# oresat0-backplane.net
KiCad netlist of a schematic drawn in EAGLE
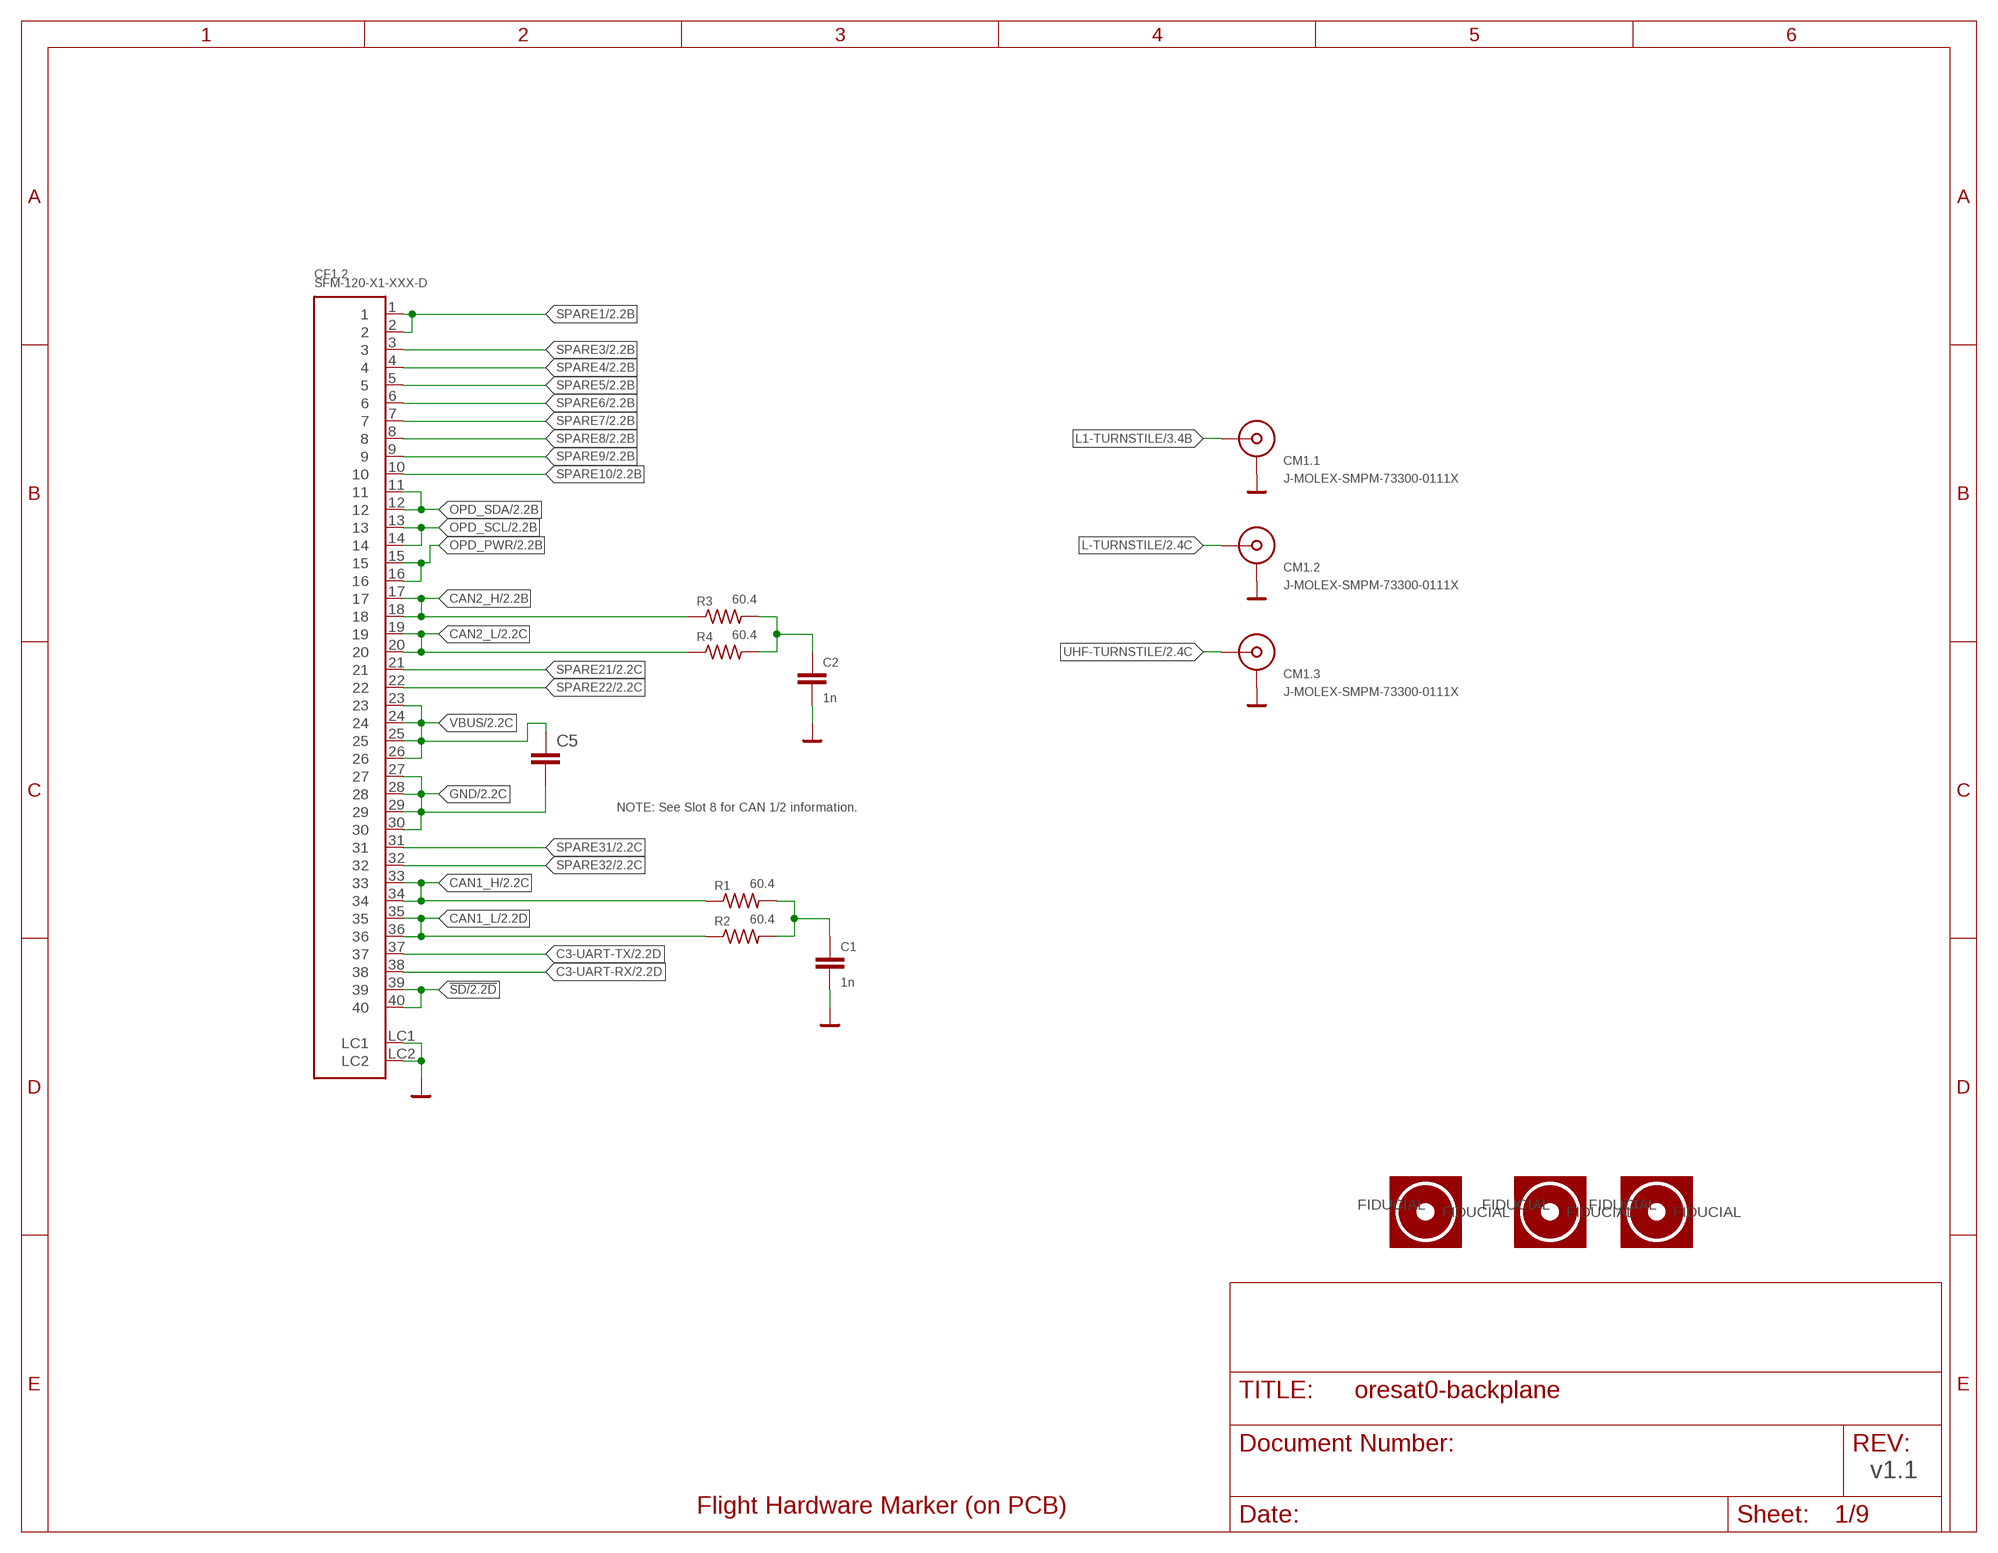
[diagram p0: schematic, sheet 1]
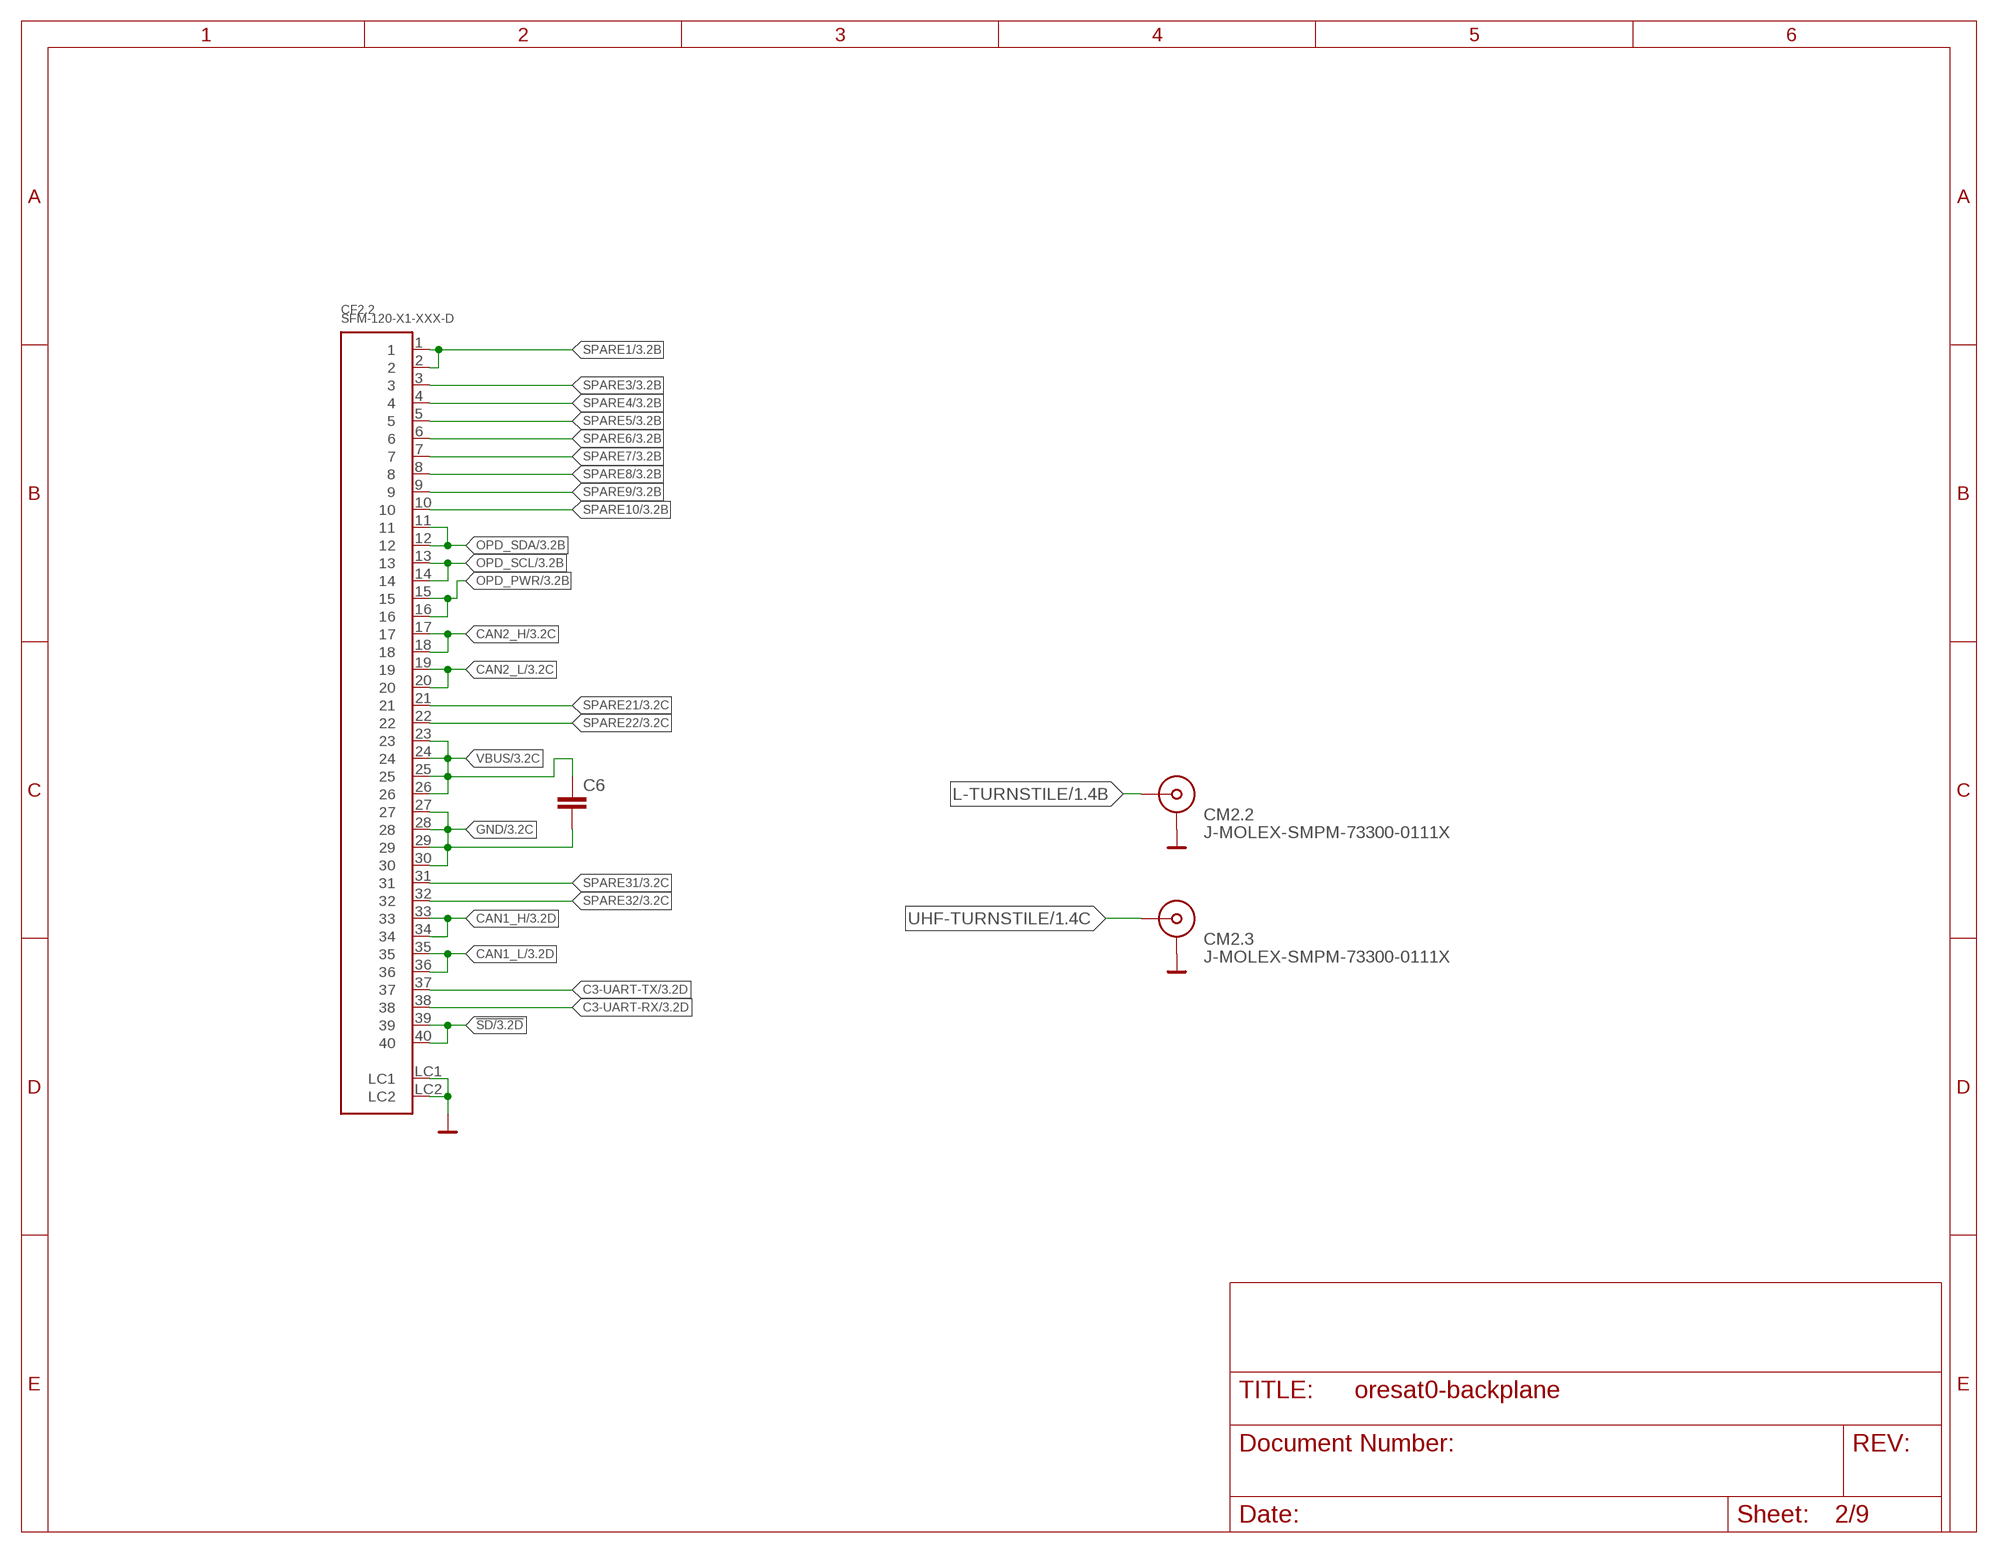
[diagram p1: schematic, sheet 2]
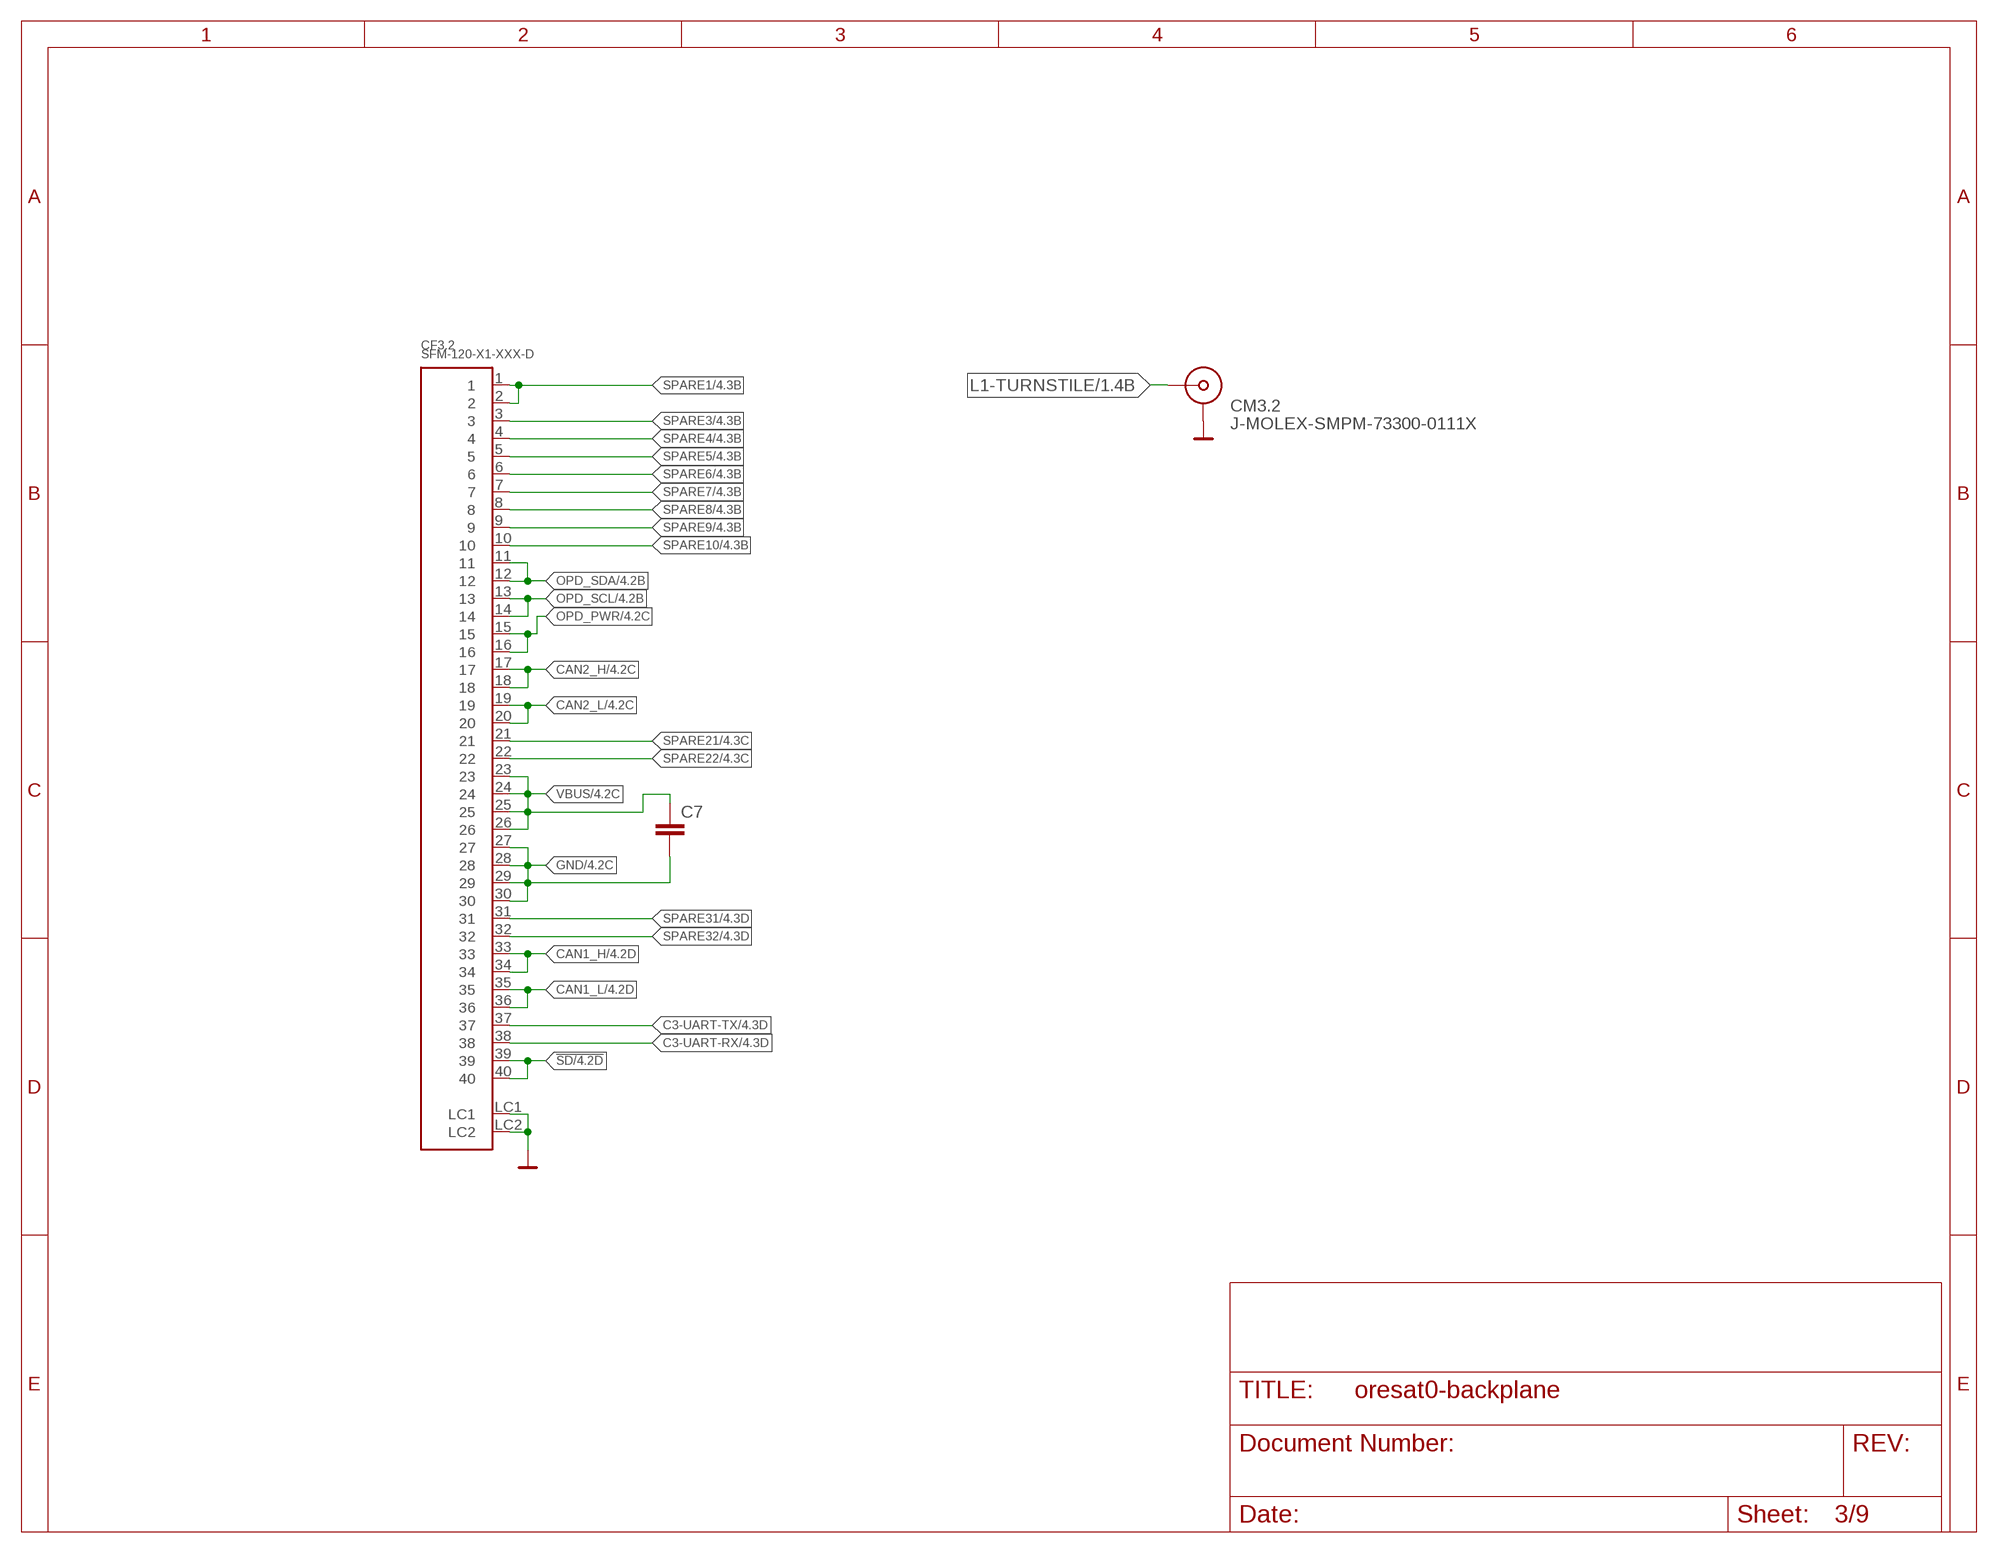
[diagram p2: schematic, sheet 3]
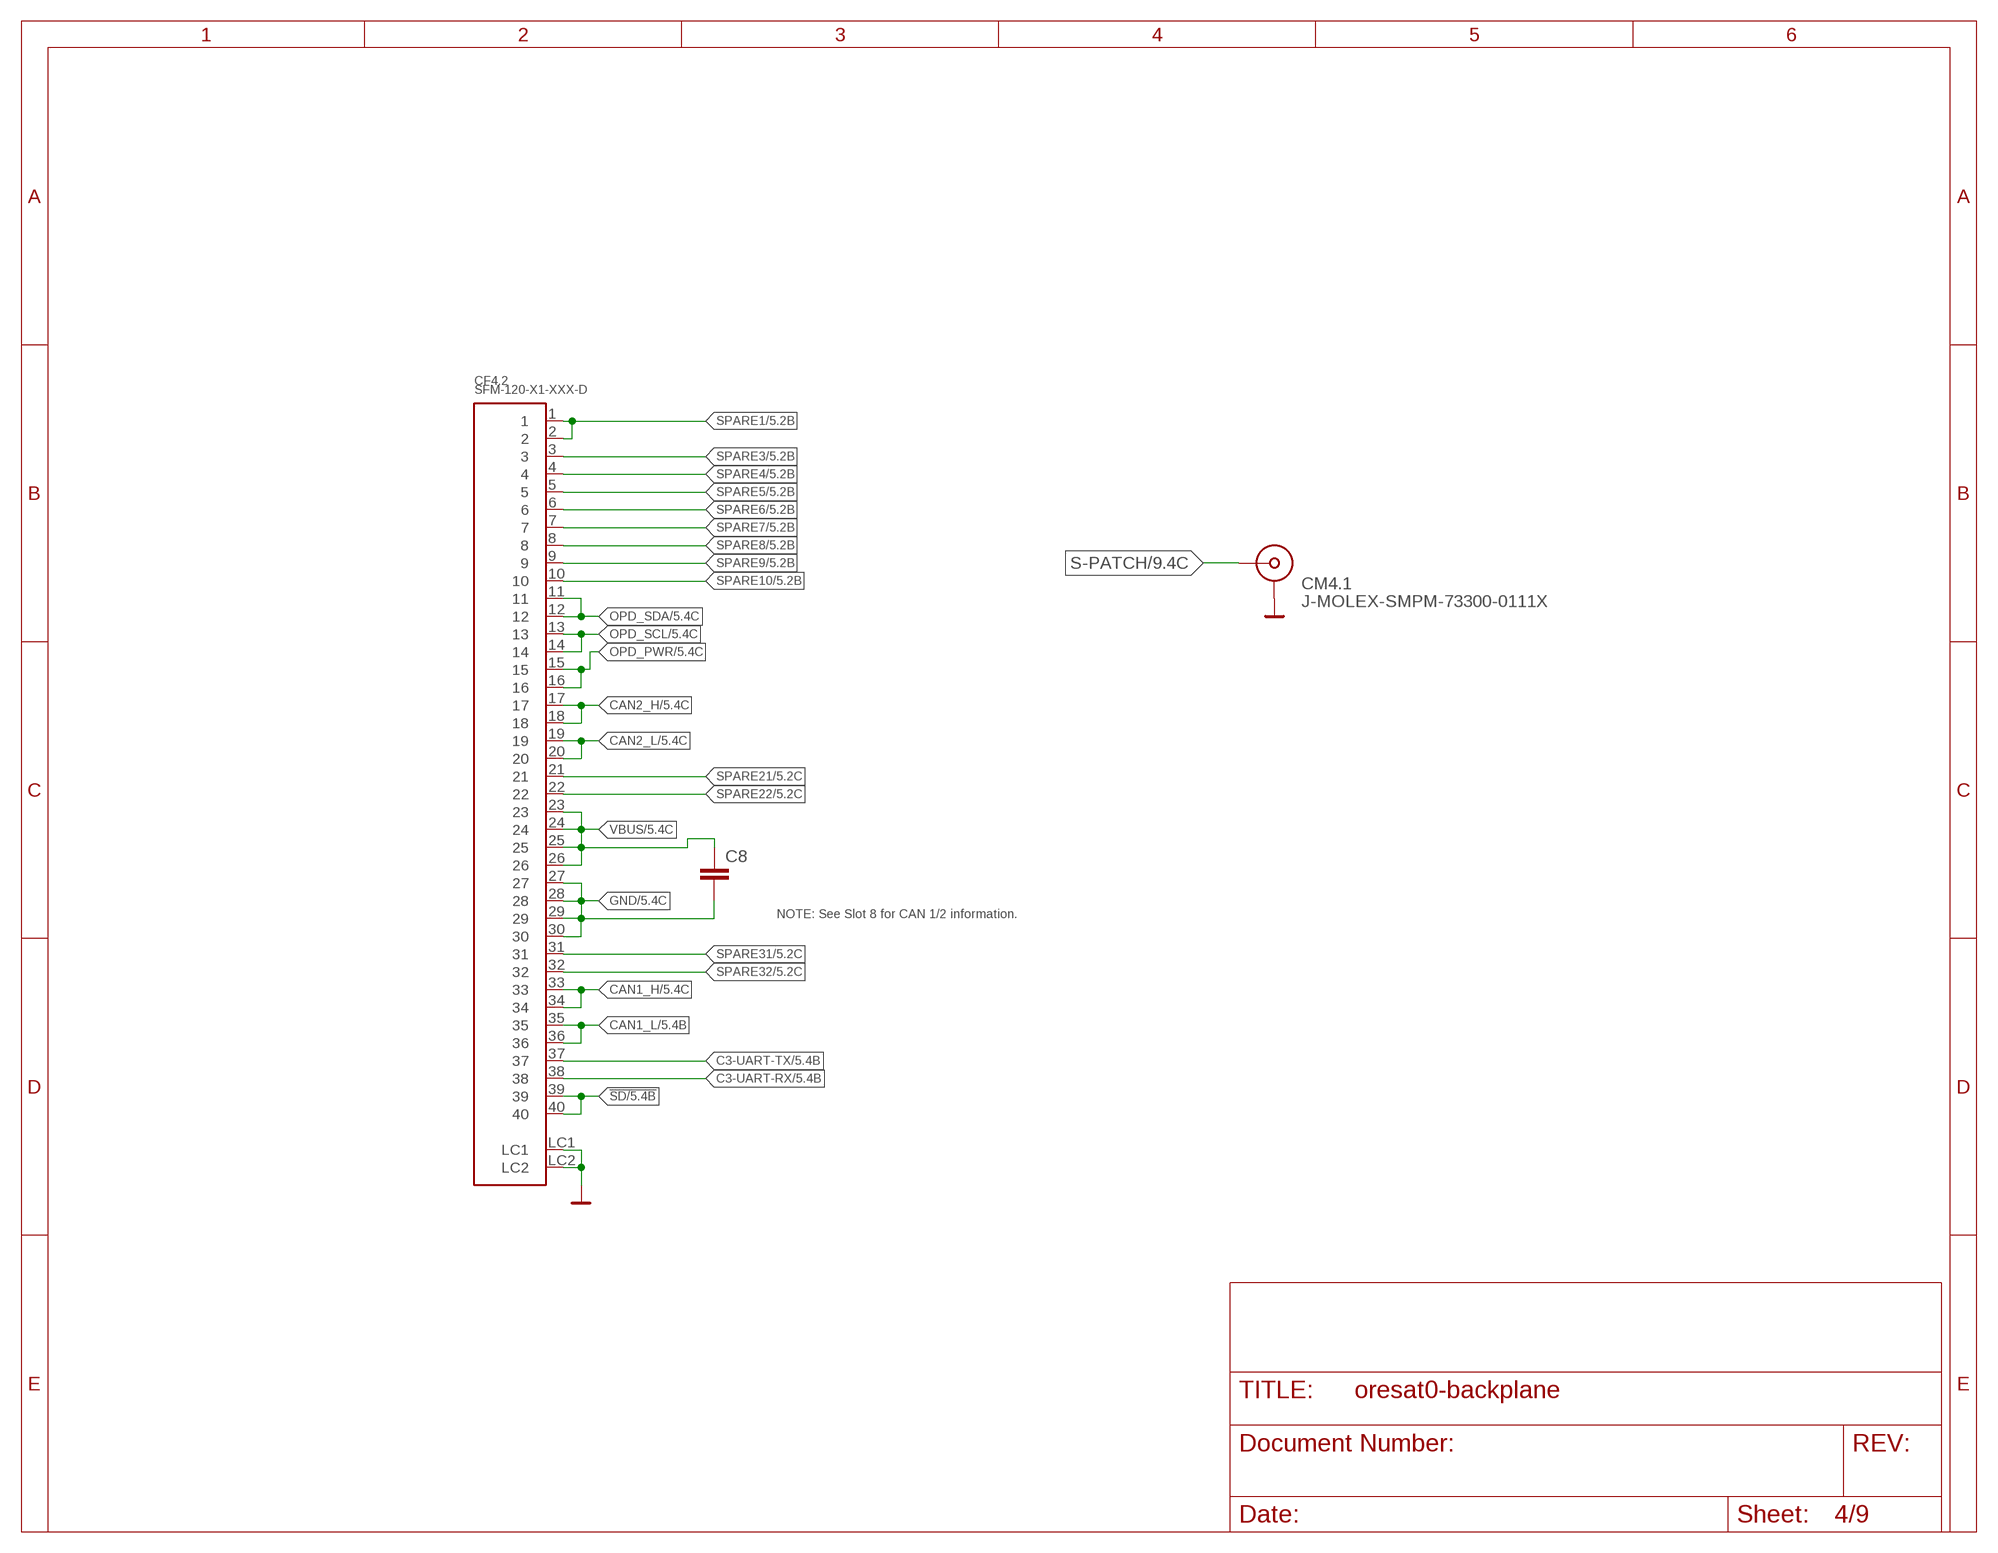
[diagram p3: schematic, sheet 4]
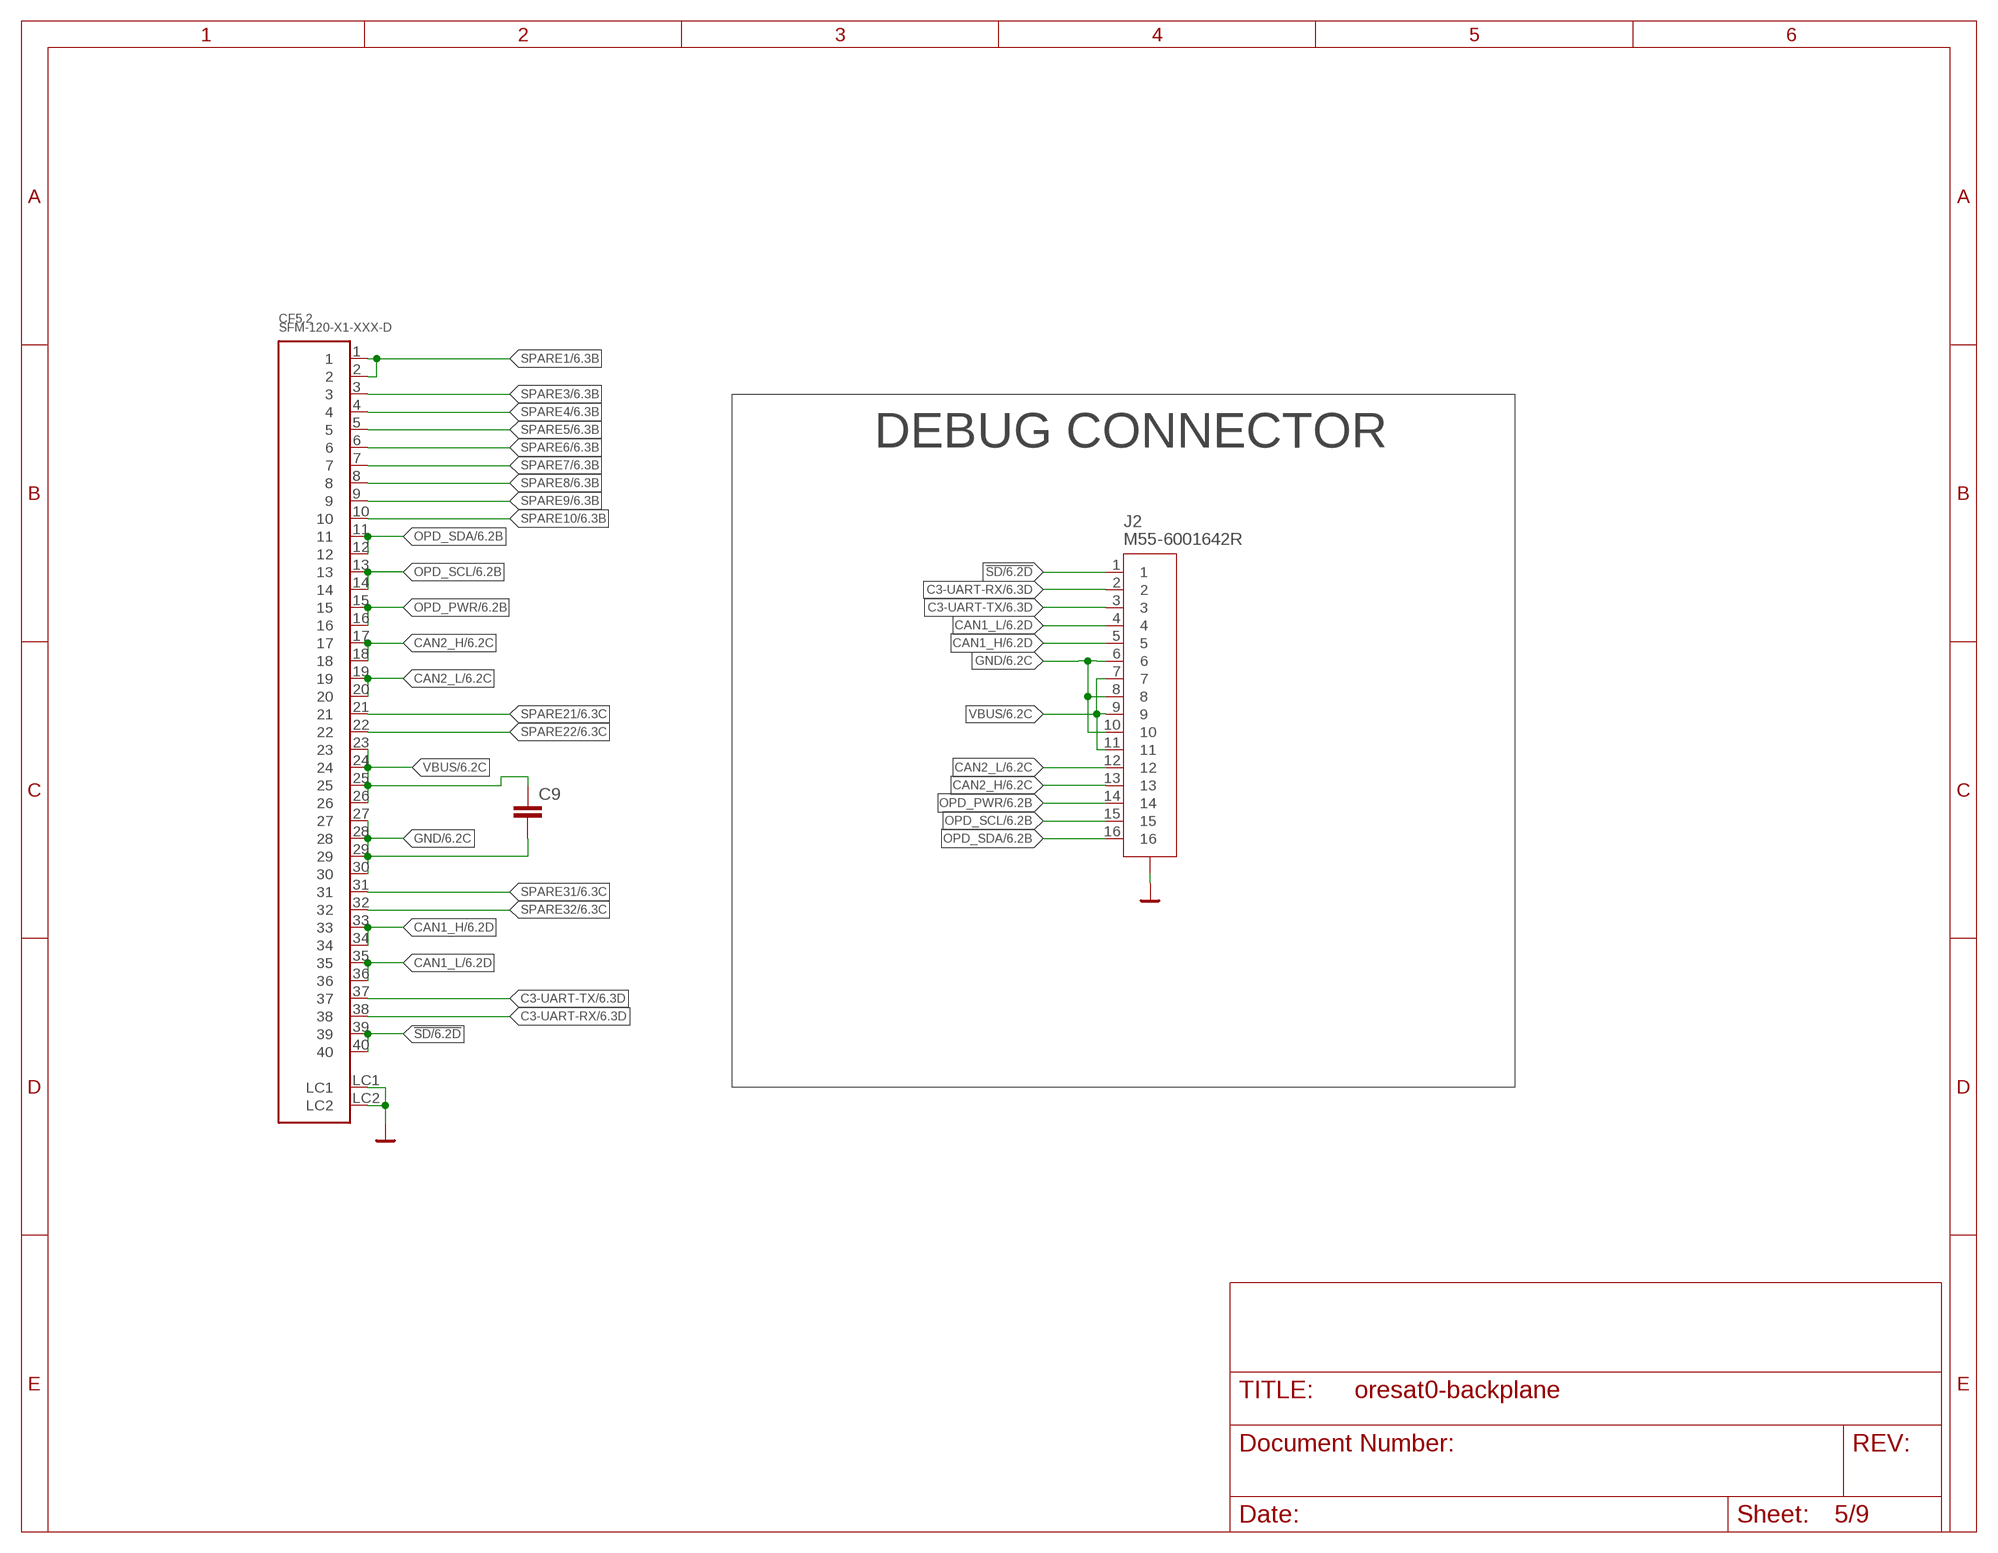
[diagram p4: schematic, sheet 5]
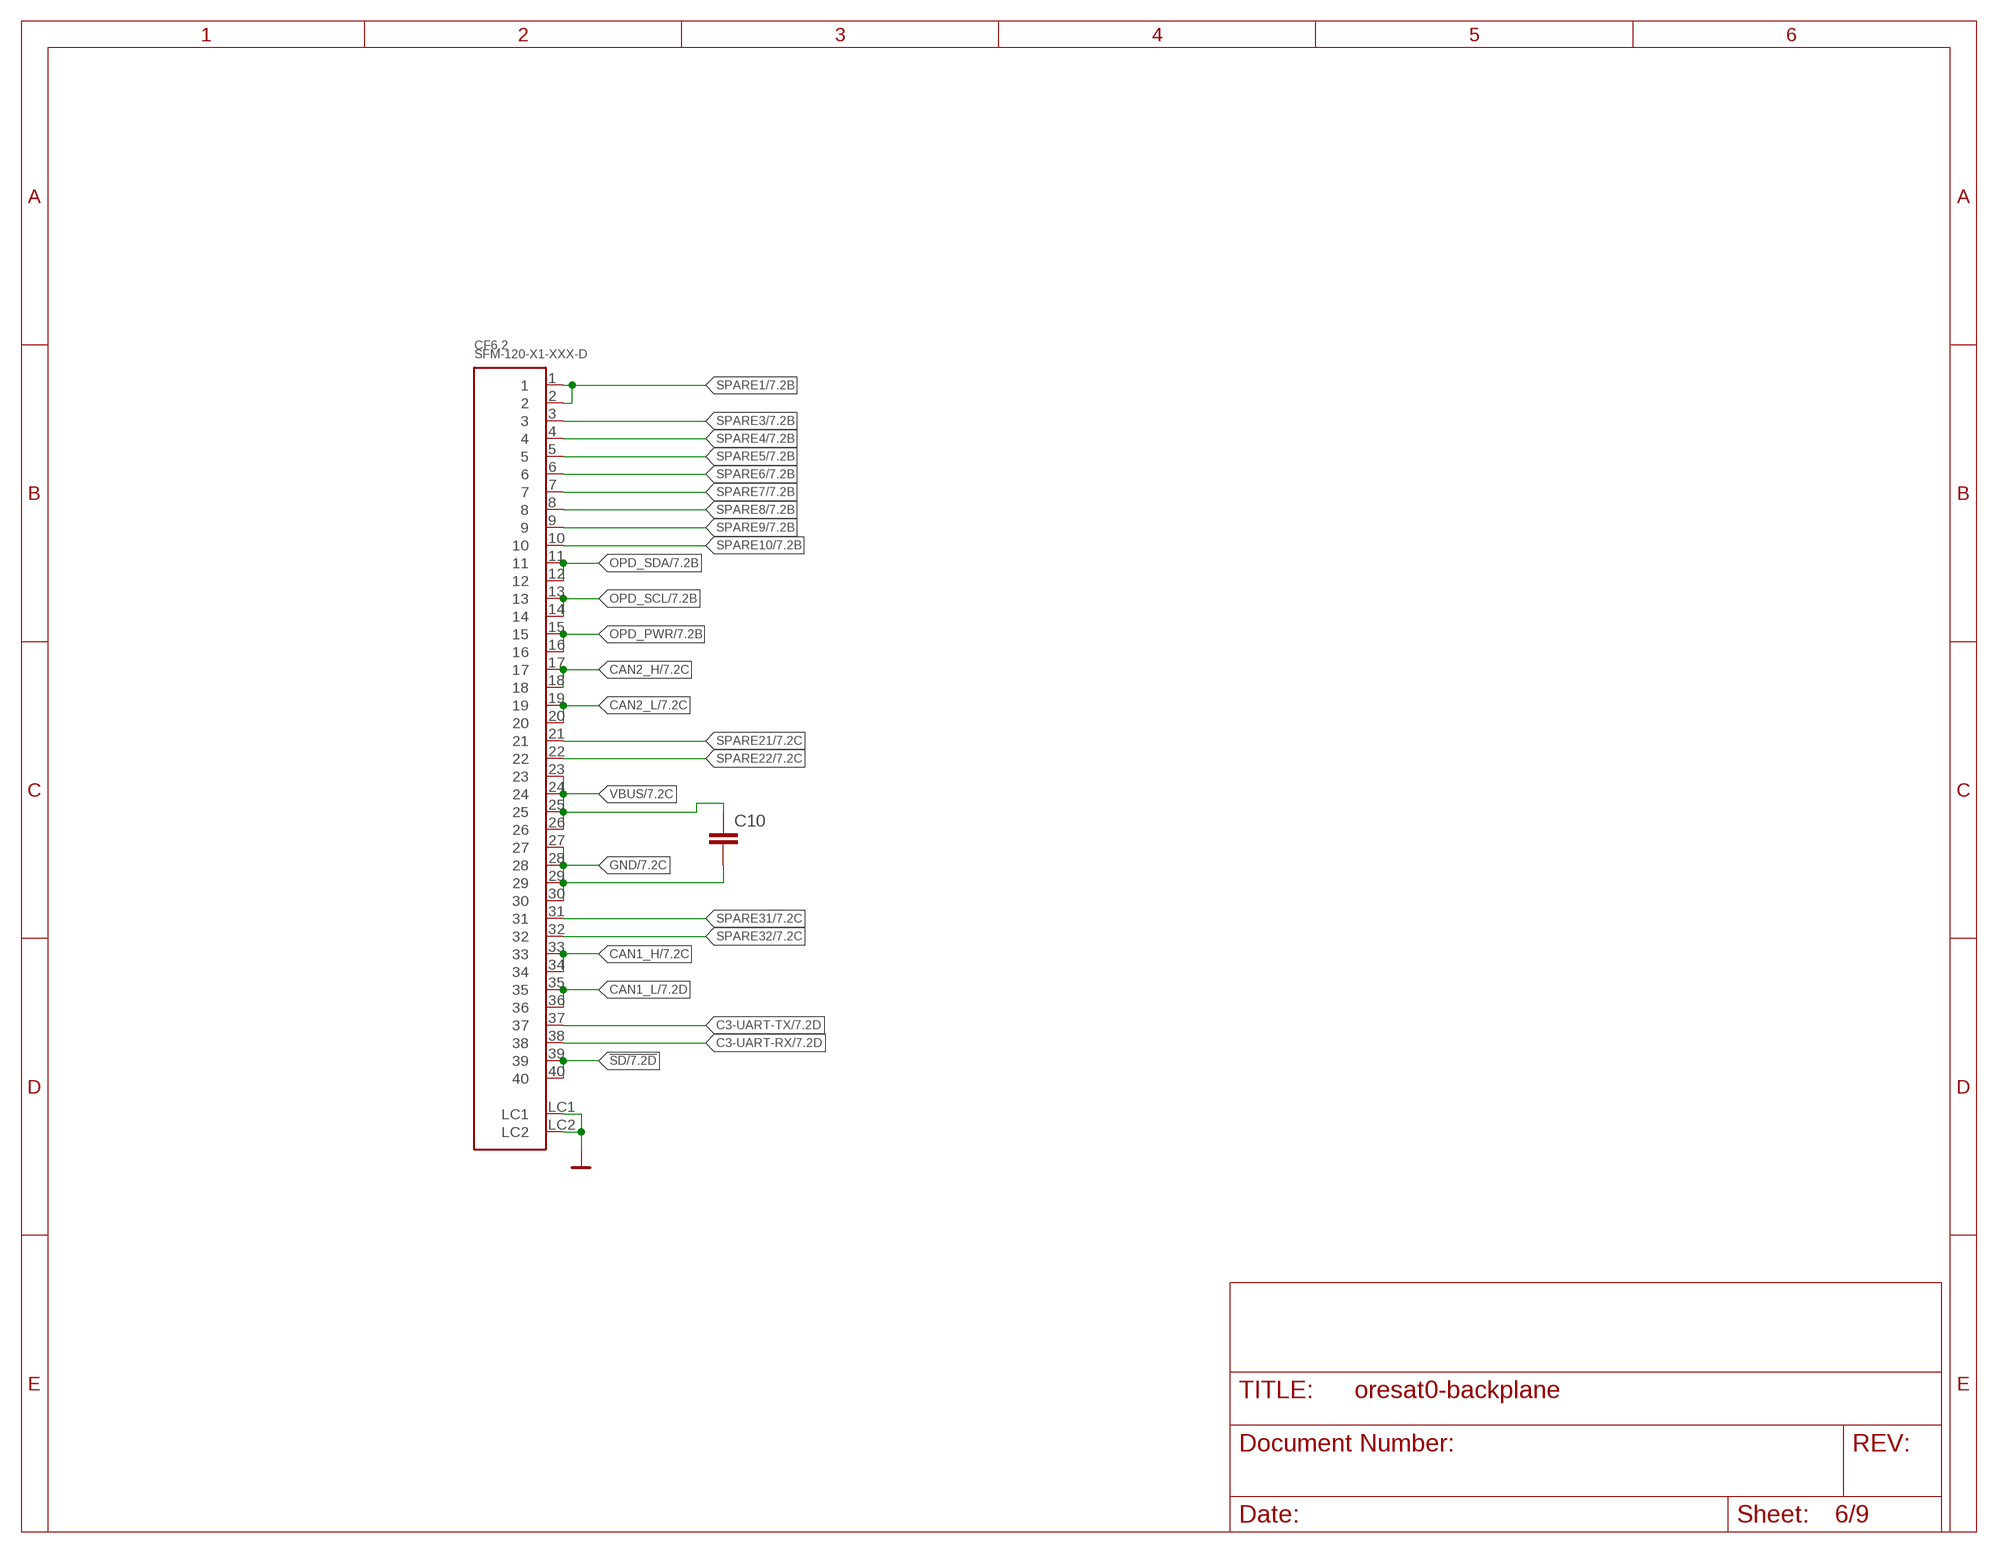
[diagram p5: schematic, sheet 6]
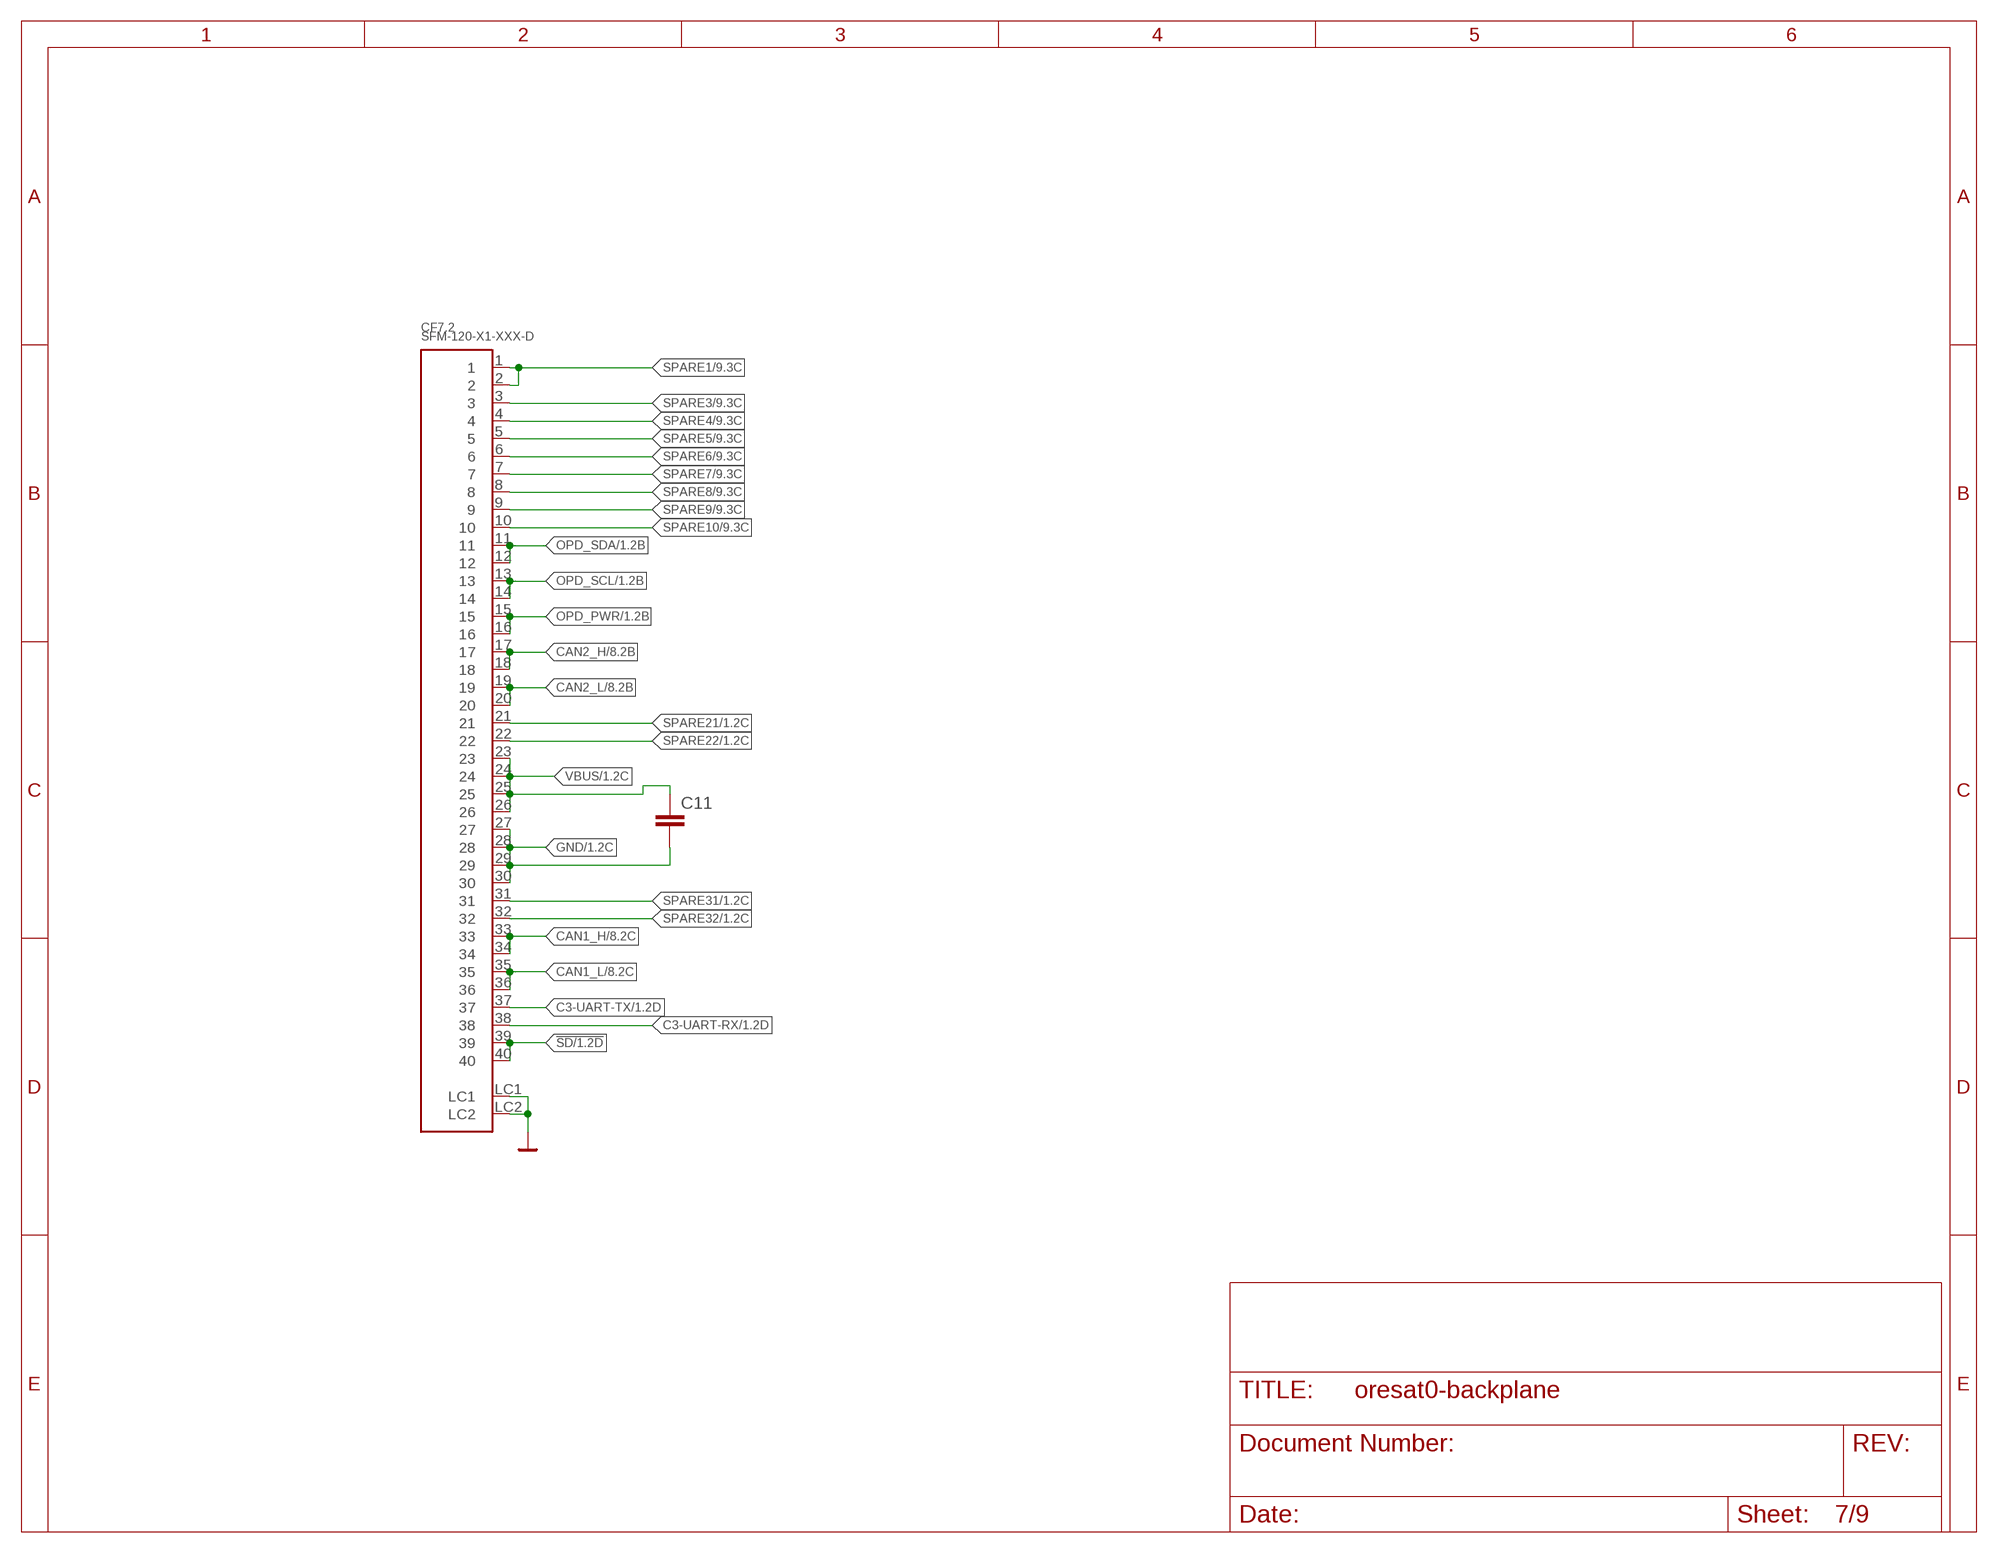
[diagram p6: schematic, sheet 7]
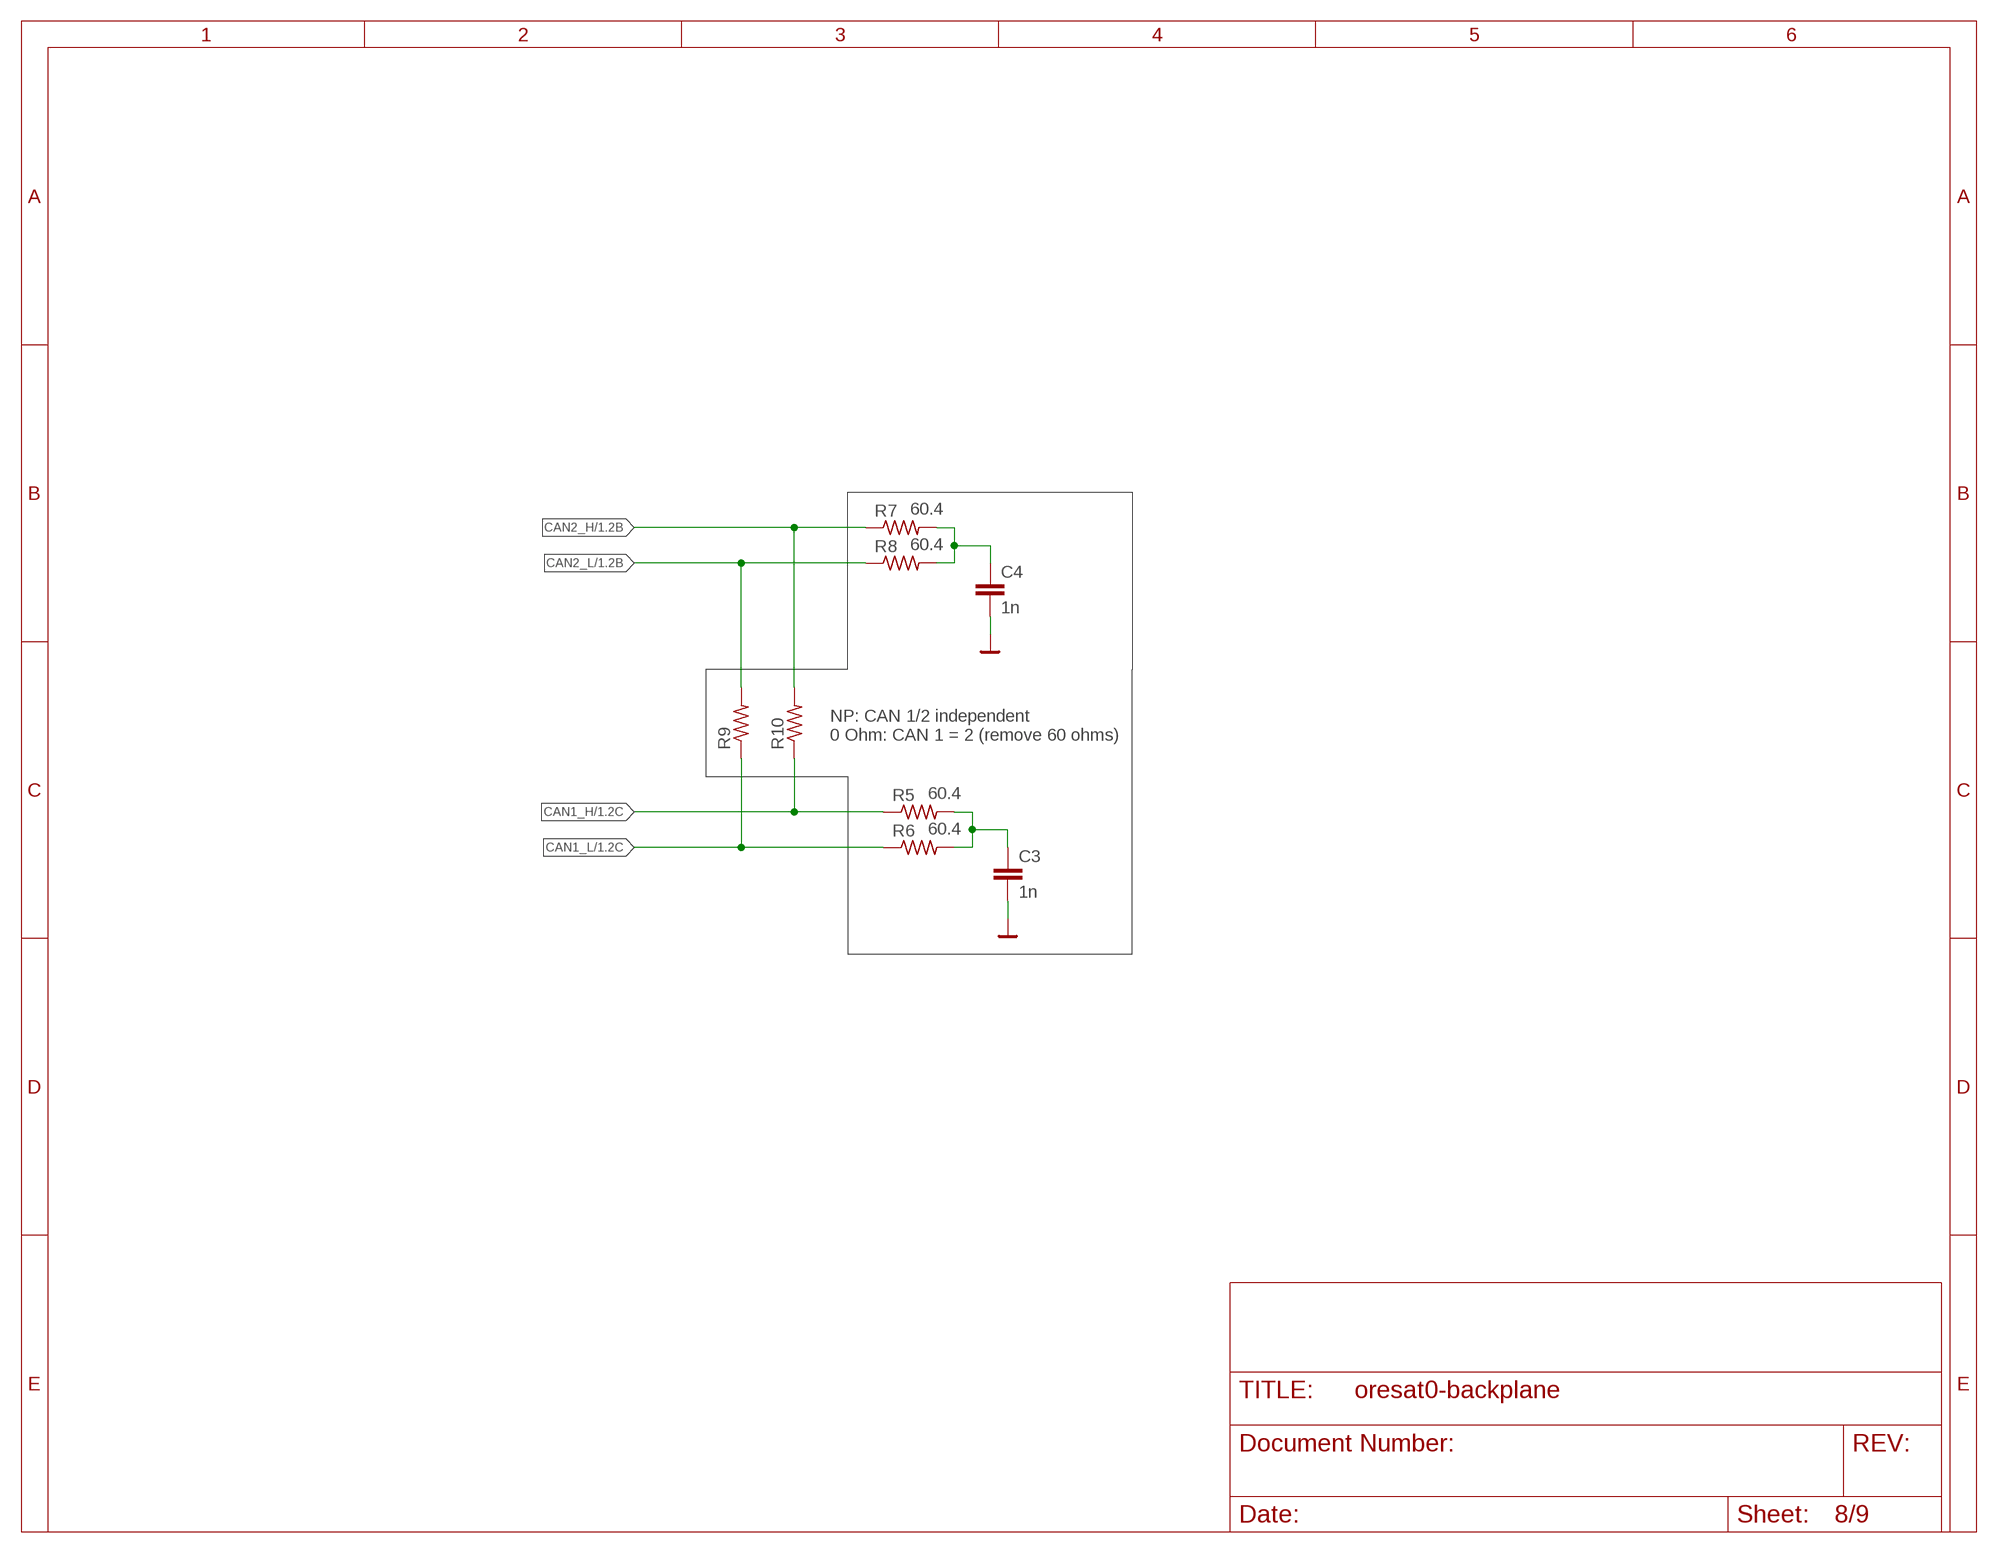
[diagram p7: schematic, sheet 8]
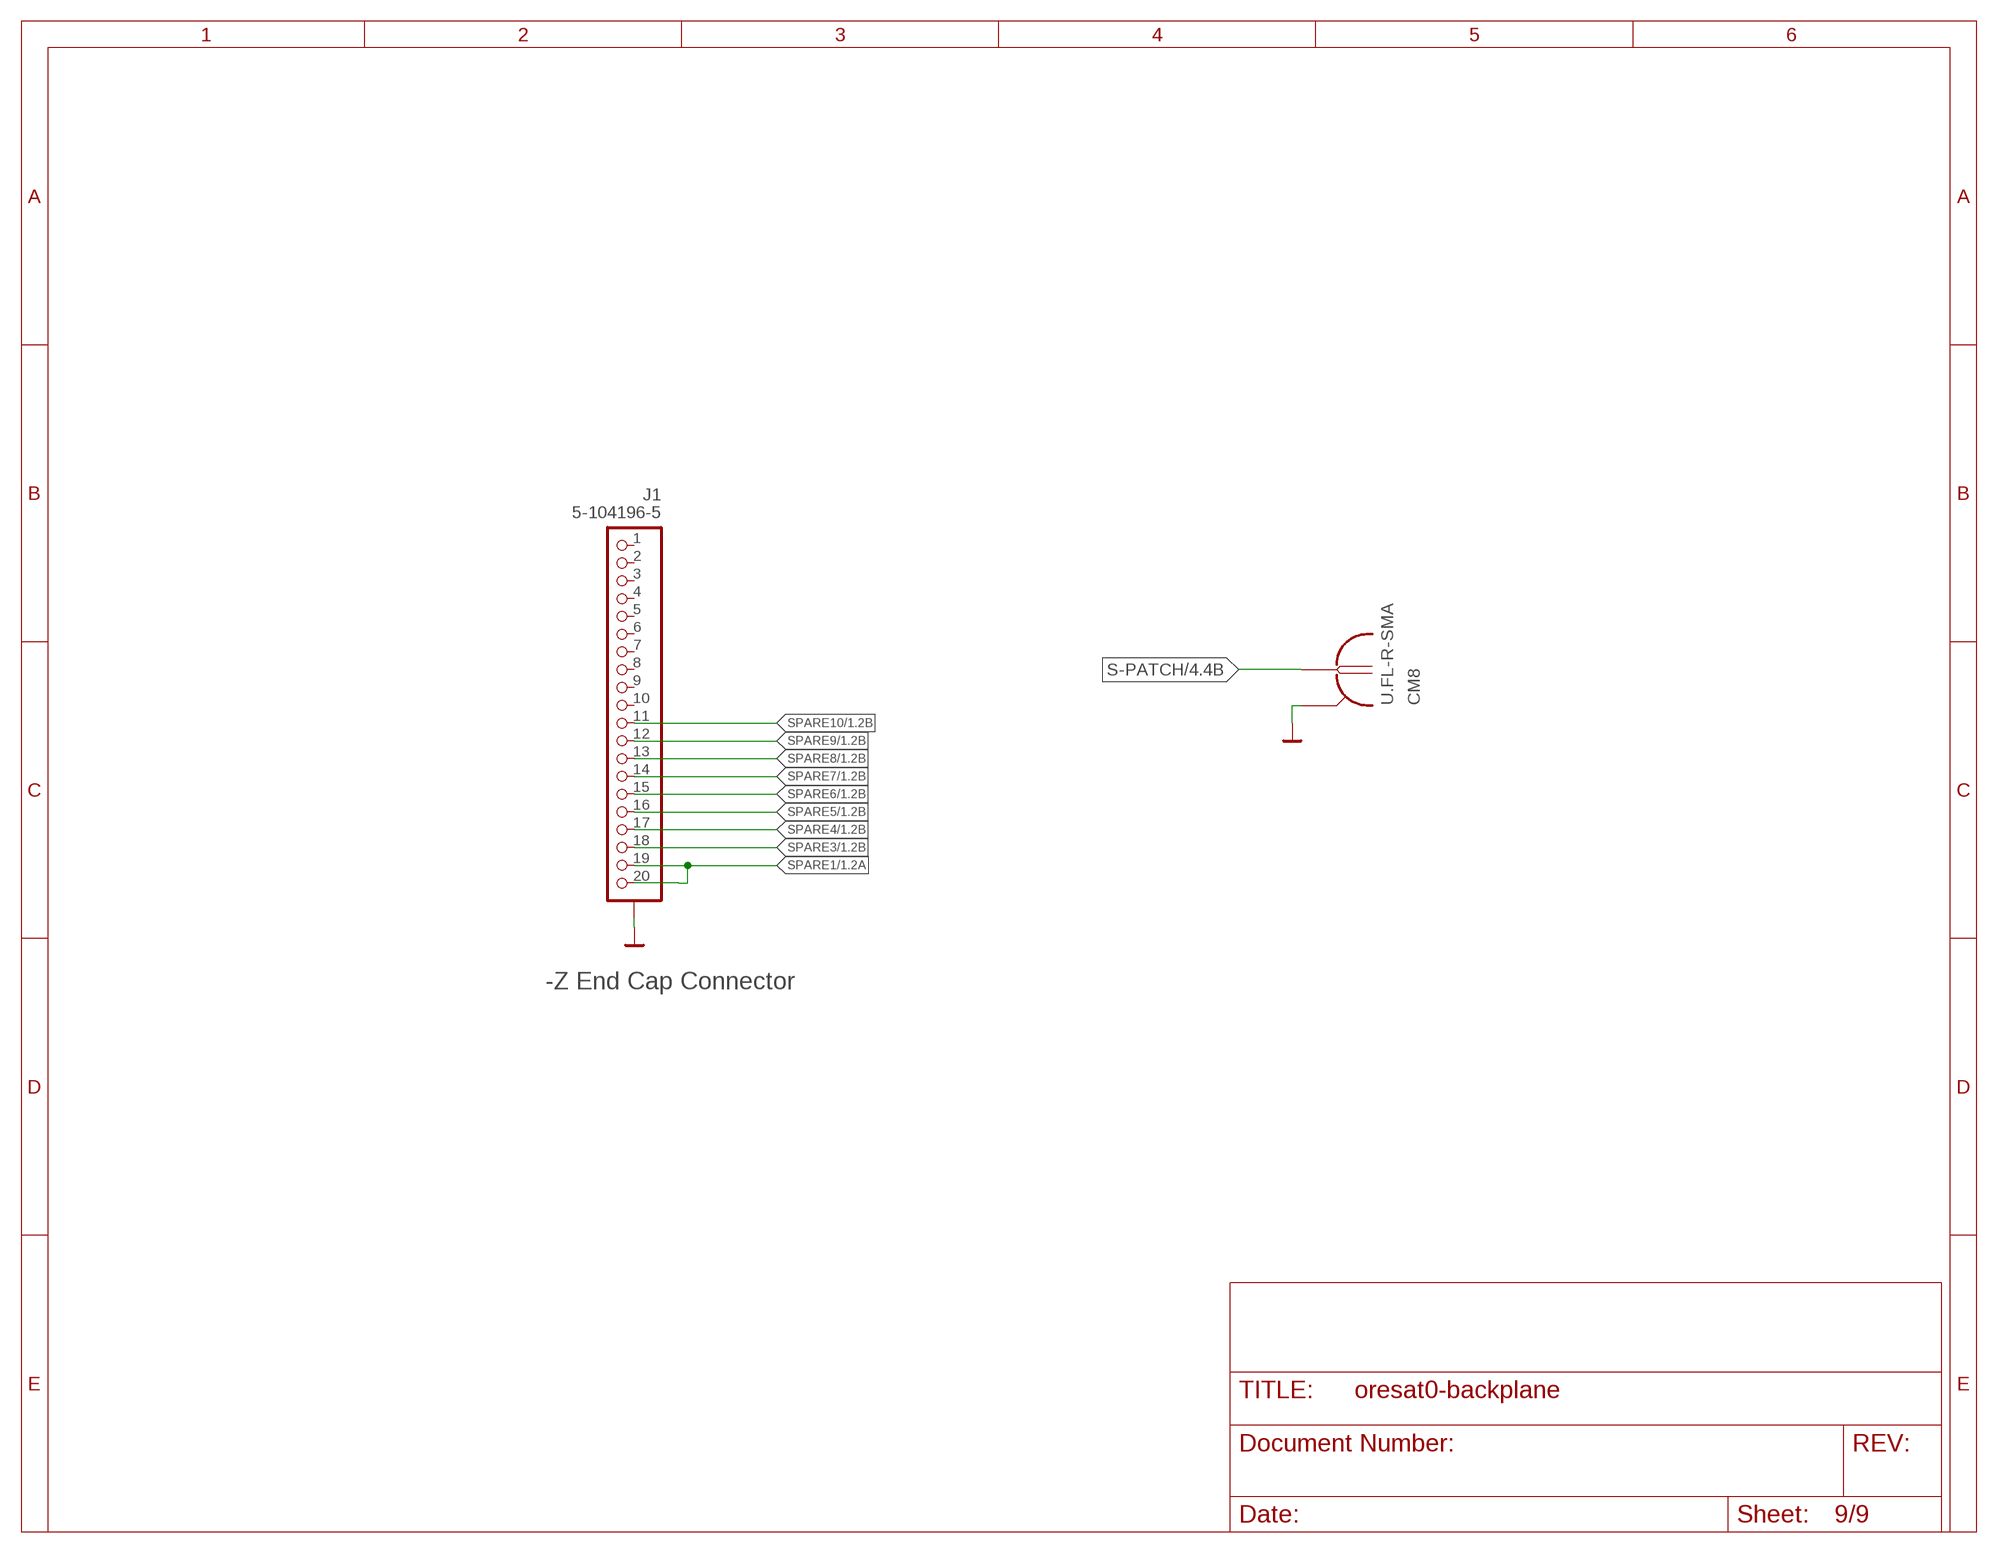
[diagram p8: schematic, sheet 9]

(export (version "E")
  (design (tool "Eeschema 10.0.6"))
  (components
    (comp (ref "C11")
      (value "C-EU1206-B")
      (footprint "eagle-import:1206-B")
      (libsource (lib "eagle-import") (part "C-EU1206-B"))
    )
    (comp (ref "CF7.2")
      (value "SFM-120-X1-XXX-D")
      (footprint "eagle-import:SFM-120-X1-XXX-D")
      (libsource (lib "eagle-import") (part "SFM-120-X1-XXX-D"))
    )
    (comp (ref "C7")
      (value "C-EU1206-B")
      (footprint "eagle-import:1206-B")
      (libsource (lib "eagle-import") (part "C-EU1206-B"))
    )
    (comp (ref "CF3.2")
      (value "SFM-120-X1-XXX-D")
      (footprint "eagle-import:SFM-120-X1-XXX-D")
      (libsource (lib "eagle-import") (part "SFM-120-X1-XXX-D"))
    )
    (comp (ref "CM3.2")
      (value "J-MOLEX-SMPM-73300-0111X")
      (footprint "eagle-import:J-MOLEX-SMPM-73300-0111X")
      (libsource (lib "eagle-import") (part "J-MOLEX-SMPM-73300-0111X"))
    )
    (comp (ref "C8")
      (value "C-EU1206-B")
      (footprint "eagle-import:1206-B")
      (libsource (lib "eagle-import") (part "C-EU1206-B"))
    )
    (comp (ref "CF4.2")
      (value "SFM-120-X1-XXX-D")
      (footprint "eagle-import:SFM-120-X1-XXX-D")
      (libsource (lib "eagle-import") (part "SFM-120-X1-XXX-D"))
    )
    (comp (ref "CM4.1")
      (value "J-MOLEX-SMPM-73300-0111X")
      (footprint "eagle-import:J-MOLEX-SMPM-73300-0111X")
      (libsource (lib "eagle-import") (part "J-MOLEX-SMPM-73300-0111X"))
    )
    (comp (ref "CM8")
      (value "U.FL-R-SMA")
      (footprint "eagle-import:U.FL-R-SMT")
      (libsource (lib "eagle-import") (part "U.FL-R-SMA"))
    )
    (comp (ref "J1")
      (value "5-104196-5")
      (footprint "eagle-import:5-104196-5")
      (libsource (lib "eagle-import") (part "5-104196-5"))
    )
    (comp (ref "C9")
      (value "C-EU1206-B")
      (footprint "eagle-import:1206-B")
      (libsource (lib "eagle-import") (part "C-EU1206-B"))
    )
    (comp (ref "CF5.2")
      (value "SFM-120-X1-XXX-D")
      (footprint "eagle-import:SFM-120-X1-XXX-D")
      (libsource (lib "eagle-import") (part "SFM-120-X1-XXX-D"))
    )
    (comp (ref "J2")
      (value "M55-6001642R")
      (footprint "eagle-import:CONN_M55-6001642R_HRW")
      (fields (field (name "COPYRIGHT") "Copyright (C) 2021 Ultra Librarian. All rights reserved."))
      (libsource (lib "eagle-import") (part "M55-6001642R"))
    )
    (comp (ref "C6")
      (value "C-EU1206-B")
      (footprint "eagle-import:1206-B")
      (libsource (lib "eagle-import") (part "C-EU1206-B"))
    )
    (comp (ref "CF2.2")
      (value "SFM-120-X1-XXX-D")
      (footprint "eagle-import:SFM-120-X1-XXX-D")
      (libsource (lib "eagle-import") (part "SFM-120-X1-XXX-D"))
    )
    (comp (ref "CM2.2")
      (value "J-MOLEX-SMPM-73300-0111X")
      (footprint "eagle-import:J-MOLEX-SMPM-73300-0111X")
      (libsource (lib "eagle-import") (part "J-MOLEX-SMPM-73300-0111X"))
    )
    (comp (ref "CM2.3")
      (value "J-MOLEX-SMPM-73300-0111X")
      (footprint "eagle-import:J-MOLEX-SMPM-73300-0111X")
      (libsource (lib "eagle-import") (part "J-MOLEX-SMPM-73300-0111X"))
    )
    (comp (ref "C1")
      (value "1n")
      (footprint "eagle-import:.0603-C-NOSILK")
      (libsource (lib "eagle-import") (part "C-EU0603-C-NOSILK"))
    )
    (comp (ref "C2")
      (value "1n")
      (footprint "eagle-import:.0603-C-NOSILK")
      (libsource (lib "eagle-import") (part "C-EU0603-C-NOSILK"))
    )
    (comp (ref "C5")
      (value "C-EU1206-B")
      (footprint "eagle-import:1206-B")
      (libsource (lib "eagle-import") (part "C-EU1206-B"))
    )
    (comp (ref "CF1.2")
      (value "SFM-120-X1-XXX-D")
      (footprint "eagle-import:SFM-120-X1-XXX-D")
      (libsource (lib "eagle-import") (part "SFM-120-X1-XXX-D"))
    )
    (comp (ref "CM1.1")
      (value "J-MOLEX-SMPM-73300-0111X")
      (footprint "eagle-import:J-MOLEX-SMPM-73300-0111X")
      (libsource (lib "eagle-import") (part "J-MOLEX-SMPM-73300-0111X"))
    )
    (comp (ref "CM1.2")
      (value "J-MOLEX-SMPM-73300-0111X")
      (footprint "eagle-import:J-MOLEX-SMPM-73300-0111X")
      (libsource (lib "eagle-import") (part "J-MOLEX-SMPM-73300-0111X"))
    )
    (comp (ref "CM1.3")
      (value "J-MOLEX-SMPM-73300-0111X")
      (footprint "eagle-import:J-MOLEX-SMPM-73300-0111X")
      (libsource (lib "eagle-import") (part "J-MOLEX-SMPM-73300-0111X"))
    )
    (comp (ref "FIDUCIAL1")
      (value "FIDUCIAL-1.0X2.0")
      (footprint "eagle-import:FIDUCIAL-1.0X2.0")
      (libsource (lib "eagle-import") (part "FIDUCIAL-1.0X2.0"))
    )
    (comp (ref "FIDUCIAL2")
      (value "FIDUCIAL-1.0X2.0")
      (footprint "eagle-import:FIDUCIAL-1.0X2.0")
      (libsource (lib "eagle-import") (part "FIDUCIAL-1.0X2.0"))
    )
    (comp (ref "FIDUCIAL3")
      (value "FIDUCIAL-1.0X2.0")
      (footprint "eagle-import:FIDUCIAL-1.0X2.0")
      (libsource (lib "eagle-import") (part "FIDUCIAL-1.0X2.0"))
    )
    (comp (ref "R1")
      (value "60.4")
      (footprint "eagle-import:1206-C")
      (libsource (lib "eagle-import") (part "R-US_1206-C"))
    )
    (comp (ref "R2")
      (value "60.4")
      (footprint "eagle-import:1206-C")
      (libsource (lib "eagle-import") (part "R-US_1206-C"))
    )
    (comp (ref "R3")
      (value "60.4")
      (footprint "eagle-import:1206-C")
      (libsource (lib "eagle-import") (part "R-US_1206-C"))
    )
    (comp (ref "R4")
      (value "60.4")
      (footprint "eagle-import:1206-C")
      (libsource (lib "eagle-import") (part "R-US_1206-C"))
    )
    (comp (ref "U$1")
      (value "FLIGHMARKERNEW")
      (footprint "eagle-import:FLIGHTMARKER_NEW_BOARDS")
      (libsource (lib "eagle-import") (part "FLIGHMARKERNEW"))
    )
    (comp (ref "C3")
      (value "1n")
      (footprint "eagle-import:.0603-C-NOSILK")
      (libsource (lib "eagle-import") (part "C-EU0603-C-NOSILK"))
    )
    (comp (ref "C4")
      (value "1n")
      (footprint "eagle-import:.0603-C-NOSILK")
      (libsource (lib "eagle-import") (part "C-EU0603-C-NOSILK"))
    )
    (comp (ref "R5")
      (value "60.4")
      (footprint "eagle-import:1206-C")
      (libsource (lib "eagle-import") (part "R-US_1206-C"))
    )
    (comp (ref "R6")
      (value "60.4")
      (footprint "eagle-import:1206-C")
      (libsource (lib "eagle-import") (part "R-US_1206-C"))
    )
    (comp (ref "R7")
      (value "60.4")
      (footprint "eagle-import:1206-C")
      (libsource (lib "eagle-import") (part "R-US_1206-C"))
    )
    (comp (ref "R8")
      (value "60.4")
      (footprint "eagle-import:1206-C")
      (libsource (lib "eagle-import") (part "R-US_1206-C"))
    )
    (comp (ref "R9")
      (value "R-US_0603-B-NOSILK")
      (footprint "eagle-import:.0603-B-NOSILK")
      (libsource (lib "eagle-import") (part "R-US_0603-B-NOSILK"))
    )
    (comp (ref "R10")
      (value "R-US_0603-B-NOSILK")
      (footprint "eagle-import:.0603-B-NOSILK")
      (libsource (lib "eagle-import") (part "R-US_0603-B-NOSILK"))
    )
    (comp (ref "C10")
      (value "C-EU1206-B")
      (footprint "eagle-import:1206-B")
      (libsource (lib "eagle-import") (part "C-EU1206-B"))
    )
    (comp (ref "CF6.2")
      (value "SFM-120-X1-XXX-D")
      (footprint "eagle-import:SFM-120-X1-XXX-D")
      (libsource (lib "eagle-import") (part "SFM-120-X1-XXX-D"))
    )
  )
  (nets
    (net (code "1") (name "C3-UART-RX") (class "Default")
      (node (ref "CF1.2") (pin "38") (pinfunction "38_38") (pintype "passive"))
      (node (ref "CF2.2") (pin "38") (pinfunction "38_38") (pintype "passive"))
      (node (ref "CF3.2") (pin "38") (pinfunction "38_38") (pintype "passive"))
      (node (ref "CF4.2") (pin "38") (pinfunction "38_38") (pintype "passive"))
      (node (ref "CF5.2") (pin "38") (pinfunction "38_38") (pintype "passive"))
      (node (ref "CF6.2") (pin "38") (pinfunction "38_38") (pintype "passive"))
      (node (ref "CF7.2") (pin "38") (pinfunction "38_38") (pintype "passive"))
      (node (ref "J2") (pin "2") (pinfunction "2_2") (pintype "passive"))
    )
    (net (code "2") (name "C3-UART-TX") (class "Default")
      (node (ref "CF1.2") (pin "37") (pinfunction "37_37") (pintype "passive"))
      (node (ref "CF2.2") (pin "37") (pinfunction "37_37") (pintype "passive"))
      (node (ref "CF3.2") (pin "37") (pinfunction "37_37") (pintype "passive"))
      (node (ref "CF4.2") (pin "37") (pinfunction "37_37") (pintype "passive"))
      (node (ref "CF5.2") (pin "37") (pinfunction "37_37") (pintype "passive"))
      (node (ref "CF6.2") (pin "37") (pinfunction "37_37") (pintype "passive"))
      (node (ref "CF7.2") (pin "37") (pinfunction "37_37") (pintype "passive"))
      (node (ref "J2") (pin "3") (pinfunction "3_3") (pintype "passive"))
    )
    (net (code "3") (name "CAN1_H") (class "Default")
      (node (ref "CF1.2") (pin "33") (pinfunction "33_33") (pintype "passive"))
      (node (ref "CF1.2") (pin "34") (pinfunction "34_34") (pintype "passive"))
      (node (ref "CF2.2") (pin "33") (pinfunction "33_33") (pintype "passive"))
      (node (ref "CF2.2") (pin "34") (pinfunction "34_34") (pintype "passive"))
      (node (ref "CF3.2") (pin "33") (pinfunction "33_33") (pintype "passive"))
      (node (ref "CF3.2") (pin "34") (pinfunction "34_34") (pintype "passive"))
      (node (ref "CF4.2") (pin "33") (pinfunction "33_33") (pintype "passive"))
      (node (ref "CF4.2") (pin "34") (pinfunction "34_34") (pintype "passive"))
      (node (ref "CF5.2") (pin "33") (pinfunction "33_33") (pintype "passive"))
      (node (ref "CF5.2") (pin "34") (pinfunction "34_34") (pintype "passive"))
      (node (ref "CF6.2") (pin "33") (pinfunction "33_33") (pintype "passive"))
      (node (ref "CF6.2") (pin "34") (pinfunction "34_34") (pintype "passive"))
      (node (ref "CF7.2") (pin "33") (pinfunction "33_33") (pintype "passive"))
      (node (ref "CF7.2") (pin "34") (pinfunction "34_34") (pintype "passive"))
      (node (ref "J2") (pin "5") (pinfunction "5_5") (pintype "passive"))
      (node (ref "R1") (pin "1") (pinfunction "1_1") (pintype "passive"))
      (node (ref "R10") (pin "1") (pinfunction "1_1") (pintype "passive"))
      (node (ref "R5") (pin "1") (pinfunction "1_1") (pintype "passive"))
    )
    (net (code "4") (name "CAN1_L") (class "Default")
      (node (ref "CF1.2") (pin "35") (pinfunction "35_35") (pintype "passive"))
      (node (ref "CF1.2") (pin "36") (pinfunction "36_36") (pintype "passive"))
      (node (ref "CF2.2") (pin "35") (pinfunction "35_35") (pintype "passive"))
      (node (ref "CF2.2") (pin "36") (pinfunction "36_36") (pintype "passive"))
      (node (ref "CF3.2") (pin "35") (pinfunction "35_35") (pintype "passive"))
      (node (ref "CF3.2") (pin "36") (pinfunction "36_36") (pintype "passive"))
      (node (ref "CF4.2") (pin "35") (pinfunction "35_35") (pintype "passive"))
      (node (ref "CF4.2") (pin "36") (pinfunction "36_36") (pintype "passive"))
      (node (ref "CF5.2") (pin "35") (pinfunction "35_35") (pintype "passive"))
      (node (ref "CF5.2") (pin "36") (pinfunction "36_36") (pintype "passive"))
      (node (ref "CF6.2") (pin "35") (pinfunction "35_35") (pintype "passive"))
      (node (ref "CF6.2") (pin "36") (pinfunction "36_36") (pintype "passive"))
      (node (ref "CF7.2") (pin "35") (pinfunction "35_35") (pintype "passive"))
      (node (ref "CF7.2") (pin "36") (pinfunction "36_36") (pintype "passive"))
      (node (ref "J2") (pin "4") (pinfunction "4_4") (pintype "passive"))
      (node (ref "R2") (pin "1") (pinfunction "1_1") (pintype "passive"))
      (node (ref "R6") (pin "1") (pinfunction "1_1") (pintype "passive"))
      (node (ref "R9") (pin "1") (pinfunction "1_1") (pintype "passive"))
    )
    (net (code "5") (name "CAN2_H") (class "Default")
      (node (ref "CF1.2") (pin "17") (pinfunction "17_17") (pintype "passive"))
      (node (ref "CF1.2") (pin "18") (pinfunction "18_18") (pintype "passive"))
      (node (ref "CF2.2") (pin "17") (pinfunction "17_17") (pintype "passive"))
      (node (ref "CF2.2") (pin "18") (pinfunction "18_18") (pintype "passive"))
      (node (ref "CF3.2") (pin "17") (pinfunction "17_17") (pintype "passive"))
      (node (ref "CF3.2") (pin "18") (pinfunction "18_18") (pintype "passive"))
      (node (ref "CF4.2") (pin "17") (pinfunction "17_17") (pintype "passive"))
      (node (ref "CF4.2") (pin "18") (pinfunction "18_18") (pintype "passive"))
      (node (ref "CF5.2") (pin "17") (pinfunction "17_17") (pintype "passive"))
      (node (ref "CF5.2") (pin "18") (pinfunction "18_18") (pintype "passive"))
      (node (ref "CF6.2") (pin "17") (pinfunction "17_17") (pintype "passive"))
      (node (ref "CF6.2") (pin "18") (pinfunction "18_18") (pintype "passive"))
      (node (ref "CF7.2") (pin "17") (pinfunction "17_17") (pintype "passive"))
      (node (ref "CF7.2") (pin "18") (pinfunction "18_18") (pintype "passive"))
      (node (ref "J2") (pin "13") (pinfunction "13_13") (pintype "passive"))
      (node (ref "R10") (pin "2") (pinfunction "2_2") (pintype "passive"))
      (node (ref "R3") (pin "1") (pinfunction "1_1") (pintype "passive"))
      (node (ref "R7") (pin "1") (pinfunction "1_1") (pintype "passive"))
    )
    (net (code "6") (name "CAN2_L") (class "Default")
      (node (ref "CF1.2") (pin "19") (pinfunction "19_19") (pintype "passive"))
      (node (ref "CF1.2") (pin "20") (pinfunction "20_20") (pintype "passive"))
      (node (ref "CF2.2") (pin "19") (pinfunction "19_19") (pintype "passive"))
      (node (ref "CF2.2") (pin "20") (pinfunction "20_20") (pintype "passive"))
      (node (ref "CF3.2") (pin "19") (pinfunction "19_19") (pintype "passive"))
      (node (ref "CF3.2") (pin "20") (pinfunction "20_20") (pintype "passive"))
      (node (ref "CF4.2") (pin "19") (pinfunction "19_19") (pintype "passive"))
      (node (ref "CF4.2") (pin "20") (pinfunction "20_20") (pintype "passive"))
      (node (ref "CF5.2") (pin "19") (pinfunction "19_19") (pintype "passive"))
      (node (ref "CF5.2") (pin "20") (pinfunction "20_20") (pintype "passive"))
      (node (ref "CF6.2") (pin "19") (pinfunction "19_19") (pintype "passive"))
      (node (ref "CF6.2") (pin "20") (pinfunction "20_20") (pintype "passive"))
      (node (ref "CF7.2") (pin "19") (pinfunction "19_19") (pintype "passive"))
      (node (ref "CF7.2") (pin "20") (pinfunction "20_20") (pintype "passive"))
      (node (ref "J2") (pin "12") (pinfunction "12_12") (pintype "passive"))
      (node (ref "R4") (pin "1") (pinfunction "1_1") (pintype "passive"))
      (node (ref "R8") (pin "1") (pinfunction "1_1") (pintype "passive"))
      (node (ref "R9") (pin "2") (pinfunction "2_2") (pintype "passive"))
    )
    (net (code "7") (name "GND") (class "Default")
      (node (ref "C1") (pin "2") (pinfunction "2_2") (pintype "passive"))
      (node (ref "C10") (pin "2") (pinfunction "2_2") (pintype "passive"))
      (node (ref "C11") (pin "2") (pinfunction "2_2") (pintype "passive"))
      (node (ref "C2") (pin "2") (pinfunction "2_2") (pintype "passive"))
      (node (ref "C3") (pin "2") (pinfunction "2_2") (pintype "passive"))
      (node (ref "C4") (pin "2") (pinfunction "2_2") (pintype "passive"))
      (node (ref "C5") (pin "2") (pinfunction "2_2") (pintype "passive"))
      (node (ref "C6") (pin "2") (pinfunction "2_2") (pintype "passive"))
      (node (ref "C7") (pin "2") (pinfunction "2_2") (pintype "passive"))
      (node (ref "C8") (pin "2") (pinfunction "2_2") (pintype "passive"))
      (node (ref "C9") (pin "2") (pinfunction "2_2") (pintype "passive"))
      (node (ref "CF1.2") (pin "27") (pinfunction "27_27") (pintype "passive"))
      (node (ref "CF1.2") (pin "28") (pinfunction "28_28") (pintype "passive"))
      (node (ref "CF1.2") (pin "29") (pinfunction "29_29") (pintype "passive"))
      (node (ref "CF1.2") (pin "30") (pinfunction "30_30") (pintype "passive"))
      (node (ref "CF1.2") (pin "LC1") (pinfunction "LC1_LC1") (pintype "passive"))
      (node (ref "CF1.2") (pin "LC2") (pinfunction "LC2_LC2") (pintype "passive"))
      (node (ref "CF2.2") (pin "27") (pinfunction "27_27") (pintype "passive"))
      (node (ref "CF2.2") (pin "28") (pinfunction "28_28") (pintype "passive"))
      (node (ref "CF2.2") (pin "29") (pinfunction "29_29") (pintype "passive"))
      (node (ref "CF2.2") (pin "30") (pinfunction "30_30") (pintype "passive"))
      (node (ref "CF2.2") (pin "LC1") (pinfunction "LC1_LC1") (pintype "passive"))
      (node (ref "CF2.2") (pin "LC2") (pinfunction "LC2_LC2") (pintype "passive"))
      (node (ref "CF3.2") (pin "27") (pinfunction "27_27") (pintype "passive"))
      (node (ref "CF3.2") (pin "28") (pinfunction "28_28") (pintype "passive"))
      (node (ref "CF3.2") (pin "29") (pinfunction "29_29") (pintype "passive"))
      (node (ref "CF3.2") (pin "30") (pinfunction "30_30") (pintype "passive"))
      (node (ref "CF3.2") (pin "LC1") (pinfunction "LC1_LC1") (pintype "passive"))
      (node (ref "CF3.2") (pin "LC2") (pinfunction "LC2_LC2") (pintype "passive"))
      (node (ref "CF4.2") (pin "27") (pinfunction "27_27") (pintype "passive"))
      (node (ref "CF4.2") (pin "28") (pinfunction "28_28") (pintype "passive"))
      (node (ref "CF4.2") (pin "29") (pinfunction "29_29") (pintype "passive"))
      (node (ref "CF4.2") (pin "30") (pinfunction "30_30") (pintype "passive"))
      (node (ref "CF4.2") (pin "LC1") (pinfunction "LC1_LC1") (pintype "passive"))
      (node (ref "CF4.2") (pin "LC2") (pinfunction "LC2_LC2") (pintype "passive"))
      (node (ref "CF5.2") (pin "27") (pinfunction "27_27") (pintype "passive"))
      (node (ref "CF5.2") (pin "28") (pinfunction "28_28") (pintype "passive"))
      (node (ref "CF5.2") (pin "29") (pinfunction "29_29") (pintype "passive"))
      (node (ref "CF5.2") (pin "30") (pinfunction "30_30") (pintype "passive"))
      (node (ref "CF5.2") (pin "LC1") (pinfunction "LC1_LC1") (pintype "passive"))
      (node (ref "CF5.2") (pin "LC2") (pinfunction "LC2_LC2") (pintype "passive"))
      (node (ref "CF6.2") (pin "27") (pinfunction "27_27") (pintype "passive"))
      (node (ref "CF6.2") (pin "28") (pinfunction "28_28") (pintype "passive"))
      (node (ref "CF6.2") (pin "29") (pinfunction "29_29") (pintype "passive"))
      (node (ref "CF6.2") (pin "30") (pinfunction "30_30") (pintype "passive"))
      (node (ref "CF6.2") (pin "LC1") (pinfunction "LC1_LC1") (pintype "passive"))
      (node (ref "CF6.2") (pin "LC2") (pinfunction "LC2_LC2") (pintype "passive"))
      (node (ref "CF7.2") (pin "27") (pinfunction "27_27") (pintype "passive"))
      (node (ref "CF7.2") (pin "28") (pinfunction "28_28") (pintype "passive"))
      (node (ref "CF7.2") (pin "29") (pinfunction "29_29") (pintype "passive"))
      (node (ref "CF7.2") (pin "30") (pinfunction "30_30") (pintype "passive"))
      (node (ref "CF7.2") (pin "LC1") (pinfunction "LC1_LC1") (pintype "passive"))
      (node (ref "CF7.2") (pin "LC2") (pinfunction "LC2_LC2") (pintype "passive"))
      (node (ref "CM1.1") (pin "P$1") (pinfunction "SHIELD1_P$1") (pintype "passive"))
      (node (ref "CM1.1") (pin "P$2") (pinfunction "SHIELD1_P$2") (pintype "passive"))
      (node (ref "CM1.1") (pin "P$3") (pinfunction "SHIELD1_P$3") (pintype "passive"))
      (node (ref "CM1.1") (pin "P$4") (pinfunction "SHIELD1_P$4") (pintype "passive"))
      (node (ref "CM1.2") (pin "P$1") (pinfunction "SHIELD1_P$1") (pintype "passive"))
      (node (ref "CM1.2") (pin "P$2") (pinfunction "SHIELD1_P$2") (pintype "passive"))
      (node (ref "CM1.2") (pin "P$3") (pinfunction "SHIELD1_P$3") (pintype "passive"))
      (node (ref "CM1.2") (pin "P$4") (pinfunction "SHIELD1_P$4") (pintype "passive"))
      (node (ref "CM1.3") (pin "P$1") (pinfunction "SHIELD1_P$1") (pintype "passive"))
      (node (ref "CM1.3") (pin "P$2") (pinfunction "SHIELD1_P$2") (pintype "passive"))
      (node (ref "CM1.3") (pin "P$3") (pinfunction "SHIELD1_P$3") (pintype "passive"))
      (node (ref "CM1.3") (pin "P$4") (pinfunction "SHIELD1_P$4") (pintype "passive"))
      (node (ref "CM2.2") (pin "P$1") (pinfunction "SHIELD1_P$1") (pintype "passive"))
      (node (ref "CM2.2") (pin "P$2") (pinfunction "SHIELD1_P$2") (pintype "passive"))
      (node (ref "CM2.2") (pin "P$3") (pinfunction "SHIELD1_P$3") (pintype "passive"))
      (node (ref "CM2.2") (pin "P$4") (pinfunction "SHIELD1_P$4") (pintype "passive"))
      (node (ref "CM2.3") (pin "P$1") (pinfunction "SHIELD1_P$1") (pintype "passive"))
      (node (ref "CM2.3") (pin "P$2") (pinfunction "SHIELD1_P$2") (pintype "passive"))
      (node (ref "CM2.3") (pin "P$3") (pinfunction "SHIELD1_P$3") (pintype "passive"))
      (node (ref "CM2.3") (pin "P$4") (pinfunction "SHIELD1_P$4") (pintype "passive"))
      (node (ref "CM3.2") (pin "P$1") (pinfunction "SHIELD1_P$1") (pintype "passive"))
      (node (ref "CM3.2") (pin "P$2") (pinfunction "SHIELD1_P$2") (pintype "passive"))
      (node (ref "CM3.2") (pin "P$3") (pinfunction "SHIELD1_P$3") (pintype "passive"))
      (node (ref "CM3.2") (pin "P$4") (pinfunction "SHIELD1_P$4") (pintype "passive"))
      (node (ref "CM4.1") (pin "P$1") (pinfunction "SHIELD1_P$1") (pintype "passive"))
      (node (ref "CM4.1") (pin "P$2") (pinfunction "SHIELD1_P$2") (pintype "passive"))
      (node (ref "CM4.1") (pin "P$3") (pinfunction "SHIELD1_P$3") (pintype "passive"))
      (node (ref "CM4.1") (pin "P$4") (pinfunction "SHIELD1_P$4") (pintype "passive"))
      (node (ref "CM8") (pin "2") (pinfunction "P$2_2") (pintype "bidirectional"))
      (node (ref "CM8") (pin "3") (pinfunction "P$2_3") (pintype "bidirectional"))
      (node (ref "J1") (pin "HD1") (pinfunction "HD_HD1") (pintype "passive"))
      (node (ref "J1") (pin "HD2") (pinfunction "HD_HD2") (pintype "passive"))
      (node (ref "J1") (pin "HD3") (pinfunction "HD_HD3") (pintype "passive"))
      (node (ref "J2") (pin "10") (pinfunction "10_10") (pintype "passive"))
      (node (ref "J2") (pin "19") (pinfunction "17_19") (pintype "passive"))
      (node (ref "J2") (pin "20") (pinfunction "17_20") (pintype "passive"))
      (node (ref "J2") (pin "21") (pinfunction "17_21") (pintype "passive"))
      (node (ref "J2") (pin "22") (pinfunction "17_22") (pintype "passive"))
      (node (ref "J2") (pin "6") (pinfunction "6_6") (pintype "passive"))
      (node (ref "J2") (pin "8") (pinfunction "8_8") (pintype "passive"))
    )
    (net (code "8") (name "L-TURNSTILE") (class "Default")
      (node (ref "CM1.2") (pin "RF-DOWN") (pinfunction "RF_RF-DOWN") (pintype "passive"))
      (node (ref "CM2.2") (pin "RF-DOWN") (pinfunction "RF_RF-DOWN") (pintype "passive"))
    )
    (net (code "9") (name "L1-TURNSTILE") (class "Default")
      (node (ref "CM1.1") (pin "RF-DOWN") (pinfunction "RF_RF-DOWN") (pintype "passive"))
      (node (ref "CM3.2") (pin "RF-DOWN") (pinfunction "RF_RF-DOWN") (pintype "passive"))
    )
    (net (code "10") (name "Net-(C1-Pad1)") (class "Default")
      (node (ref "C1") (pin "1") (pinfunction "1_1") (pintype "passive"))
      (node (ref "R1") (pin "2") (pinfunction "2_2") (pintype "passive"))
      (node (ref "R2") (pin "2") (pinfunction "2_2") (pintype "passive"))
    )
    (net (code "11") (name "Net-(C2-Pad1)") (class "Default")
      (node (ref "C2") (pin "1") (pinfunction "1_1") (pintype "passive"))
      (node (ref "R3") (pin "2") (pinfunction "2_2") (pintype "passive"))
      (node (ref "R4") (pin "2") (pinfunction "2_2") (pintype "passive"))
    )
    (net (code "12") (name "Net-(C3-Pad1)") (class "Default")
      (node (ref "C3") (pin "1") (pinfunction "1_1") (pintype "passive"))
      (node (ref "R5") (pin "2") (pinfunction "2_2") (pintype "passive"))
      (node (ref "R6") (pin "2") (pinfunction "2_2") (pintype "passive"))
    )
    (net (code "13") (name "Net-(C4-Pad1)") (class "Default")
      (node (ref "C4") (pin "1") (pinfunction "1_1") (pintype "passive"))
      (node (ref "R7") (pin "2") (pinfunction "2_2") (pintype "passive"))
      (node (ref "R8") (pin "2") (pinfunction "2_2") (pintype "passive"))
    )
    (net (code "14") (name "OPD_PWR") (class "Default")
      (node (ref "CF1.2") (pin "15") (pinfunction "15_15") (pintype "passive"))
      (node (ref "CF1.2") (pin "16") (pinfunction "16_16") (pintype "passive"))
      (node (ref "CF2.2") (pin "15") (pinfunction "15_15") (pintype "passive"))
      (node (ref "CF2.2") (pin "16") (pinfunction "16_16") (pintype "passive"))
      (node (ref "CF3.2") (pin "15") (pinfunction "15_15") (pintype "passive"))
      (node (ref "CF3.2") (pin "16") (pinfunction "16_16") (pintype "passive"))
      (node (ref "CF4.2") (pin "15") (pinfunction "15_15") (pintype "passive"))
      (node (ref "CF4.2") (pin "16") (pinfunction "16_16") (pintype "passive"))
      (node (ref "CF5.2") (pin "15") (pinfunction "15_15") (pintype "passive"))
      (node (ref "CF5.2") (pin "16") (pinfunction "16_16") (pintype "passive"))
      (node (ref "CF6.2") (pin "15") (pinfunction "15_15") (pintype "passive"))
      (node (ref "CF6.2") (pin "16") (pinfunction "16_16") (pintype "passive"))
      (node (ref "CF7.2") (pin "15") (pinfunction "15_15") (pintype "passive"))
      (node (ref "CF7.2") (pin "16") (pinfunction "16_16") (pintype "passive"))
      (node (ref "J2") (pin "14") (pinfunction "14_14") (pintype "passive"))
    )
    (net (code "15") (name "OPD_SCL") (class "Default")
      (node (ref "CF1.2") (pin "13") (pinfunction "13_13") (pintype "passive"))
      (node (ref "CF1.2") (pin "14") (pinfunction "14_14") (pintype "passive"))
      (node (ref "CF2.2") (pin "13") (pinfunction "13_13") (pintype "passive"))
      (node (ref "CF2.2") (pin "14") (pinfunction "14_14") (pintype "passive"))
      (node (ref "CF3.2") (pin "13") (pinfunction "13_13") (pintype "passive"))
      (node (ref "CF3.2") (pin "14") (pinfunction "14_14") (pintype "passive"))
      (node (ref "CF4.2") (pin "13") (pinfunction "13_13") (pintype "passive"))
      (node (ref "CF4.2") (pin "14") (pinfunction "14_14") (pintype "passive"))
      (node (ref "CF5.2") (pin "13") (pinfunction "13_13") (pintype "passive"))
      (node (ref "CF5.2") (pin "14") (pinfunction "14_14") (pintype "passive"))
      (node (ref "CF6.2") (pin "13") (pinfunction "13_13") (pintype "passive"))
      (node (ref "CF6.2") (pin "14") (pinfunction "14_14") (pintype "passive"))
      (node (ref "CF7.2") (pin "13") (pinfunction "13_13") (pintype "passive"))
      (node (ref "CF7.2") (pin "14") (pinfunction "14_14") (pintype "passive"))
      (node (ref "J2") (pin "15") (pinfunction "15_15") (pintype "passive"))
    )
    (net (code "16") (name "OPD_SDA") (class "Default")
      (node (ref "CF1.2") (pin "11") (pinfunction "11_11") (pintype "passive"))
      (node (ref "CF1.2") (pin "12") (pinfunction "12_12") (pintype "passive"))
      (node (ref "CF2.2") (pin "11") (pinfunction "11_11") (pintype "passive"))
      (node (ref "CF2.2") (pin "12") (pinfunction "12_12") (pintype "passive"))
      (node (ref "CF3.2") (pin "11") (pinfunction "11_11") (pintype "passive"))
      (node (ref "CF3.2") (pin "12") (pinfunction "12_12") (pintype "passive"))
      (node (ref "CF4.2") (pin "11") (pinfunction "11_11") (pintype "passive"))
      (node (ref "CF4.2") (pin "12") (pinfunction "12_12") (pintype "passive"))
      (node (ref "CF5.2") (pin "11") (pinfunction "11_11") (pintype "passive"))
      (node (ref "CF5.2") (pin "12") (pinfunction "12_12") (pintype "passive"))
      (node (ref "CF6.2") (pin "11") (pinfunction "11_11") (pintype "passive"))
      (node (ref "CF6.2") (pin "12") (pinfunction "12_12") (pintype "passive"))
      (node (ref "CF7.2") (pin "11") (pinfunction "11_11") (pintype "passive"))
      (node (ref "CF7.2") (pin "12") (pinfunction "12_12") (pintype "passive"))
      (node (ref "J2") (pin "16") (pinfunction "16_16") (pintype "passive"))
    )
    (net (code "17") (name "S-PATCH") (class "Default")
      (node (ref "CM4.1") (pin "RF-DOWN") (pinfunction "RF_RF-DOWN") (pintype "passive"))
      (node (ref "CM8") (pin "1") (pinfunction "P$1_1") (pintype "bidirectional"))
    )
    (net (code "18") (name "SPARE1") (class "Default")
      (node (ref "CF1.2") (pin "1") (pinfunction "1_1") (pintype "passive"))
      (node (ref "CF1.2") (pin "2") (pinfunction "2_2") (pintype "passive"))
      (node (ref "CF2.2") (pin "1") (pinfunction "1_1") (pintype "passive"))
      (node (ref "CF2.2") (pin "2") (pinfunction "2_2") (pintype "passive"))
      (node (ref "CF3.2") (pin "1") (pinfunction "1_1") (pintype "passive"))
      (node (ref "CF3.2") (pin "2") (pinfunction "2_2") (pintype "passive"))
      (node (ref "CF4.2") (pin "1") (pinfunction "1_1") (pintype "passive"))
      (node (ref "CF4.2") (pin "2") (pinfunction "2_2") (pintype "passive"))
      (node (ref "CF5.2") (pin "1") (pinfunction "1_1") (pintype "passive"))
      (node (ref "CF5.2") (pin "2") (pinfunction "2_2") (pintype "passive"))
      (node (ref "CF6.2") (pin "1") (pinfunction "1_1") (pintype "passive"))
      (node (ref "CF6.2") (pin "2") (pinfunction "2_2") (pintype "passive"))
      (node (ref "CF7.2") (pin "1") (pinfunction "1_1") (pintype "passive"))
      (node (ref "CF7.2") (pin "2") (pinfunction "2_2") (pintype "passive"))
      (node (ref "J1") (pin "19") (pinfunction "19_19") (pintype "passive"))
      (node (ref "J1") (pin "20") (pinfunction "20_20") (pintype "passive"))
    )
    (net (code "19") (name "SPARE3") (class "Default")
      (node (ref "CF1.2") (pin "3") (pinfunction "3_3") (pintype "passive"))
      (node (ref "CF2.2") (pin "3") (pinfunction "3_3") (pintype "passive"))
      (node (ref "CF3.2") (pin "3") (pinfunction "3_3") (pintype "passive"))
      (node (ref "CF4.2") (pin "3") (pinfunction "3_3") (pintype "passive"))
      (node (ref "CF5.2") (pin "3") (pinfunction "3_3") (pintype "passive"))
      (node (ref "CF6.2") (pin "3") (pinfunction "3_3") (pintype "passive"))
      (node (ref "CF7.2") (pin "3") (pinfunction "3_3") (pintype "passive"))
      (node (ref "J1") (pin "18") (pinfunction "18_18") (pintype "passive"))
    )
    (net (code "20") (name "SPARE4") (class "Default")
      (node (ref "CF1.2") (pin "4") (pinfunction "4_4") (pintype "passive"))
      (node (ref "CF2.2") (pin "4") (pinfunction "4_4") (pintype "passive"))
      (node (ref "CF3.2") (pin "4") (pinfunction "4_4") (pintype "passive"))
      (node (ref "CF4.2") (pin "4") (pinfunction "4_4") (pintype "passive"))
      (node (ref "CF5.2") (pin "4") (pinfunction "4_4") (pintype "passive"))
      (node (ref "CF6.2") (pin "4") (pinfunction "4_4") (pintype "passive"))
      (node (ref "CF7.2") (pin "4") (pinfunction "4_4") (pintype "passive"))
      (node (ref "J1") (pin "17") (pinfunction "17_17") (pintype "passive"))
    )
    (net (code "21") (name "SPARE5") (class "Default")
      (node (ref "CF1.2") (pin "5") (pinfunction "5_5") (pintype "passive"))
      (node (ref "CF2.2") (pin "5") (pinfunction "5_5") (pintype "passive"))
      (node (ref "CF3.2") (pin "5") (pinfunction "5_5") (pintype "passive"))
      (node (ref "CF4.2") (pin "5") (pinfunction "5_5") (pintype "passive"))
      (node (ref "CF5.2") (pin "5") (pinfunction "5_5") (pintype "passive"))
      (node (ref "CF6.2") (pin "5") (pinfunction "5_5") (pintype "passive"))
      (node (ref "CF7.2") (pin "5") (pinfunction "5_5") (pintype "passive"))
      (node (ref "J1") (pin "16") (pinfunction "16_16") (pintype "passive"))
    )
    (net (code "22") (name "SPARE6") (class "Default")
      (node (ref "CF1.2") (pin "6") (pinfunction "6_6") (pintype "passive"))
      (node (ref "CF2.2") (pin "6") (pinfunction "6_6") (pintype "passive"))
      (node (ref "CF3.2") (pin "6") (pinfunction "6_6") (pintype "passive"))
      (node (ref "CF4.2") (pin "6") (pinfunction "6_6") (pintype "passive"))
      (node (ref "CF5.2") (pin "6") (pinfunction "6_6") (pintype "passive"))
      (node (ref "CF6.2") (pin "6") (pinfunction "6_6") (pintype "passive"))
      (node (ref "CF7.2") (pin "6") (pinfunction "6_6") (pintype "passive"))
      (node (ref "J1") (pin "15") (pinfunction "15_15") (pintype "passive"))
    )
    (net (code "23") (name "SPARE7") (class "Default")
      (node (ref "CF1.2") (pin "7") (pinfunction "7_7") (pintype "passive"))
      (node (ref "CF2.2") (pin "7") (pinfunction "7_7") (pintype "passive"))
      (node (ref "CF3.2") (pin "7") (pinfunction "7_7") (pintype "passive"))
      (node (ref "CF4.2") (pin "7") (pinfunction "7_7") (pintype "passive"))
      (node (ref "CF5.2") (pin "7") (pinfunction "7_7") (pintype "passive"))
      (node (ref "CF6.2") (pin "7") (pinfunction "7_7") (pintype "passive"))
      (node (ref "CF7.2") (pin "7") (pinfunction "7_7") (pintype "passive"))
      (node (ref "J1") (pin "14") (pinfunction "14_14") (pintype "passive"))
    )
    (net (code "24") (name "SPARE8") (class "Default")
      (node (ref "CF1.2") (pin "8") (pinfunction "8_8") (pintype "passive"))
      (node (ref "CF2.2") (pin "8") (pinfunction "8_8") (pintype "passive"))
      (node (ref "CF3.2") (pin "8") (pinfunction "8_8") (pintype "passive"))
      (node (ref "CF4.2") (pin "8") (pinfunction "8_8") (pintype "passive"))
      (node (ref "CF5.2") (pin "8") (pinfunction "8_8") (pintype "passive"))
      (node (ref "CF6.2") (pin "8") (pinfunction "8_8") (pintype "passive"))
      (node (ref "CF7.2") (pin "8") (pinfunction "8_8") (pintype "passive"))
      (node (ref "J1") (pin "13") (pinfunction "13_13") (pintype "passive"))
    )
    (net (code "25") (name "SPARE9") (class "Default")
      (node (ref "CF1.2") (pin "9") (pinfunction "9_9") (pintype "passive"))
      (node (ref "CF2.2") (pin "9") (pinfunction "9_9") (pintype "passive"))
      (node (ref "CF3.2") (pin "9") (pinfunction "9_9") (pintype "passive"))
      (node (ref "CF4.2") (pin "9") (pinfunction "9_9") (pintype "passive"))
      (node (ref "CF5.2") (pin "9") (pinfunction "9_9") (pintype "passive"))
      (node (ref "CF6.2") (pin "9") (pinfunction "9_9") (pintype "passive"))
      (node (ref "CF7.2") (pin "9") (pinfunction "9_9") (pintype "passive"))
      (node (ref "J1") (pin "12") (pinfunction "12_12") (pintype "passive"))
    )
    (net (code "26") (name "SPARE10") (class "Default")
      (node (ref "CF1.2") (pin "10") (pinfunction "10_10") (pintype "passive"))
      (node (ref "CF2.2") (pin "10") (pinfunction "10_10") (pintype "passive"))
      (node (ref "CF3.2") (pin "10") (pinfunction "10_10") (pintype "passive"))
      (node (ref "CF4.2") (pin "10") (pinfunction "10_10") (pintype "passive"))
      (node (ref "CF5.2") (pin "10") (pinfunction "10_10") (pintype "passive"))
      (node (ref "CF6.2") (pin "10") (pinfunction "10_10") (pintype "passive"))
      (node (ref "CF7.2") (pin "10") (pinfunction "10_10") (pintype "passive"))
      (node (ref "J1") (pin "11") (pinfunction "11_11") (pintype "passive"))
    )
    (net (code "27") (name "SPARE21") (class "Default")
      (node (ref "CF1.2") (pin "21") (pinfunction "21_21") (pintype "passive"))
      (node (ref "CF2.2") (pin "21") (pinfunction "21_21") (pintype "passive"))
      (node (ref "CF3.2") (pin "21") (pinfunction "21_21") (pintype "passive"))
      (node (ref "CF4.2") (pin "21") (pinfunction "21_21") (pintype "passive"))
      (node (ref "CF5.2") (pin "21") (pinfunction "21_21") (pintype "passive"))
      (node (ref "CF6.2") (pin "21") (pinfunction "21_21") (pintype "passive"))
      (node (ref "CF7.2") (pin "21") (pinfunction "21_21") (pintype "passive"))
    )
    (net (code "28") (name "SPARE22") (class "Default")
      (node (ref "CF1.2") (pin "22") (pinfunction "22_22") (pintype "passive"))
      (node (ref "CF2.2") (pin "22") (pinfunction "22_22") (pintype "passive"))
      (node (ref "CF3.2") (pin "22") (pinfunction "22_22") (pintype "passive"))
      (node (ref "CF4.2") (pin "22") (pinfunction "22_22") (pintype "passive"))
      (node (ref "CF5.2") (pin "22") (pinfunction "22_22") (pintype "passive"))
      (node (ref "CF6.2") (pin "22") (pinfunction "22_22") (pintype "passive"))
      (node (ref "CF7.2") (pin "22") (pinfunction "22_22") (pintype "passive"))
    )
    (net (code "29") (name "SPARE31") (class "Default")
      (node (ref "CF1.2") (pin "31") (pinfunction "31_31") (pintype "passive"))
      (node (ref "CF2.2") (pin "31") (pinfunction "31_31") (pintype "passive"))
      (node (ref "CF3.2") (pin "31") (pinfunction "31_31") (pintype "passive"))
      (node (ref "CF4.2") (pin "31") (pinfunction "31_31") (pintype "passive"))
      (node (ref "CF5.2") (pin "31") (pinfunction "31_31") (pintype "passive"))
      (node (ref "CF6.2") (pin "31") (pinfunction "31_31") (pintype "passive"))
      (node (ref "CF7.2") (pin "31") (pinfunction "31_31") (pintype "passive"))
    )
    (net (code "30") (name "SPARE32") (class "Default")
      (node (ref "CF1.2") (pin "32") (pinfunction "32_32") (pintype "passive"))
      (node (ref "CF2.2") (pin "32") (pinfunction "32_32") (pintype "passive"))
      (node (ref "CF3.2") (pin "32") (pinfunction "32_32") (pintype "passive"))
      (node (ref "CF4.2") (pin "32") (pinfunction "32_32") (pintype "passive"))
      (node (ref "CF5.2") (pin "32") (pinfunction "32_32") (pintype "passive"))
      (node (ref "CF6.2") (pin "32") (pinfunction "32_32") (pintype "passive"))
      (node (ref "CF7.2") (pin "32") (pinfunction "32_32") (pintype "passive"))
    )
    (net (code "31") (name "UHF-TURNSTILE") (class "Default")
      (node (ref "CM1.3") (pin "RF-DOWN") (pinfunction "RF_RF-DOWN") (pintype "passive"))
      (node (ref "CM2.3") (pin "RF-DOWN") (pinfunction "RF_RF-DOWN") (pintype "passive"))
    )
    (net (code "32") (name "VBUS") (class "Default")
      (node (ref "C10") (pin "1") (pinfunction "1_1") (pintype "passive"))
      (node (ref "C11") (pin "1") (pinfunction "1_1") (pintype "passive"))
      (node (ref "C5") (pin "1") (pinfunction "1_1") (pintype "passive"))
      (node (ref "C6") (pin "1") (pinfunction "1_1") (pintype "passive"))
      (node (ref "C7") (pin "1") (pinfunction "1_1") (pintype "passive"))
      (node (ref "C8") (pin "1") (pinfunction "1_1") (pintype "passive"))
      (node (ref "C9") (pin "1") (pinfunction "1_1") (pintype "passive"))
      (node (ref "CF1.2") (pin "23") (pinfunction "23_23") (pintype "passive"))
      (node (ref "CF1.2") (pin "24") (pinfunction "24_24") (pintype "passive"))
      (node (ref "CF1.2") (pin "25") (pinfunction "25_25") (pintype "passive"))
      (node (ref "CF1.2") (pin "26") (pinfunction "26_26") (pintype "passive"))
      (node (ref "CF2.2") (pin "23") (pinfunction "23_23") (pintype "passive"))
      (node (ref "CF2.2") (pin "24") (pinfunction "24_24") (pintype "passive"))
      (node (ref "CF2.2") (pin "25") (pinfunction "25_25") (pintype "passive"))
      (node (ref "CF2.2") (pin "26") (pinfunction "26_26") (pintype "passive"))
      (node (ref "CF3.2") (pin "23") (pinfunction "23_23") (pintype "passive"))
      (node (ref "CF3.2") (pin "24") (pinfunction "24_24") (pintype "passive"))
      (node (ref "CF3.2") (pin "25") (pinfunction "25_25") (pintype "passive"))
      (node (ref "CF3.2") (pin "26") (pinfunction "26_26") (pintype "passive"))
      (node (ref "CF4.2") (pin "23") (pinfunction "23_23") (pintype "passive"))
      (node (ref "CF4.2") (pin "24") (pinfunction "24_24") (pintype "passive"))
      (node (ref "CF4.2") (pin "25") (pinfunction "25_25") (pintype "passive"))
      (node (ref "CF4.2") (pin "26") (pinfunction "26_26") (pintype "passive"))
      (node (ref "CF5.2") (pin "23") (pinfunction "23_23") (pintype "passive"))
      (node (ref "CF5.2") (pin "24") (pinfunction "24_24") (pintype "passive"))
      (node (ref "CF5.2") (pin "25") (pinfunction "25_25") (pintype "passive"))
      (node (ref "CF5.2") (pin "26") (pinfunction "26_26") (pintype "passive"))
      (node (ref "CF6.2") (pin "23") (pinfunction "23_23") (pintype "passive"))
      (node (ref "CF6.2") (pin "24") (pinfunction "24_24") (pintype "passive"))
      (node (ref "CF6.2") (pin "25") (pinfunction "25_25") (pintype "passive"))
      (node (ref "CF6.2") (pin "26") (pinfunction "26_26") (pintype "passive"))
      (node (ref "CF7.2") (pin "23") (pinfunction "23_23") (pintype "passive"))
      (node (ref "CF7.2") (pin "24") (pinfunction "24_24") (pintype "passive"))
      (node (ref "CF7.2") (pin "25") (pinfunction "25_25") (pintype "passive"))
      (node (ref "CF7.2") (pin "26") (pinfunction "26_26") (pintype "passive"))
      (node (ref "J2") (pin "11") (pinfunction "11_11") (pintype "passive"))
      (node (ref "J2") (pin "7") (pinfunction "7_7") (pintype "passive"))
      (node (ref "J2") (pin "9") (pinfunction "9_9") (pintype "passive"))
    )
    (net (code "33") (name "unconnected-(FIDUCIAL1-PadFIDUCIAL)") (class "Default")
      (node (ref "FIDUCIAL1") (pin "FIDUCIAL") (pinfunction "FIDUCIAL_FIDUCIAL") (pintype "no_connect"))
    )
    (net (code "34") (name "unconnected-(FIDUCIAL2-PadFIDUCIAL)") (class "Default")
      (node (ref "FIDUCIAL2") (pin "FIDUCIAL") (pinfunction "FIDUCIAL_FIDUCIAL") (pintype "no_connect"))
    )
    (net (code "35") (name "unconnected-(FIDUCIAL3-PadFIDUCIAL)") (class "Default")
      (node (ref "FIDUCIAL3") (pin "FIDUCIAL") (pinfunction "FIDUCIAL_FIDUCIAL") (pintype "no_connect"))
    )
    (net (code "36") (name "unconnected-(J1-Pad1)") (class "Default")
      (node (ref "J1") (pin "1") (pinfunction "1_1") (pintype "passive"))
    )
    (net (code "37") (name "unconnected-(J1-Pad2)") (class "Default")
      (node (ref "J1") (pin "2") (pinfunction "2_2") (pintype "passive"))
    )
    (net (code "38") (name "unconnected-(J1-Pad3)") (class "Default")
      (node (ref "J1") (pin "3") (pinfunction "3_3") (pintype "passive"))
    )
    (net (code "39") (name "unconnected-(J1-Pad4)") (class "Default")
      (node (ref "J1") (pin "4") (pinfunction "4_4") (pintype "passive"))
    )
    (net (code "40") (name "unconnected-(J1-Pad5)") (class "Default")
      (node (ref "J1") (pin "5") (pinfunction "5_5") (pintype "passive"))
    )
    (net (code "41") (name "unconnected-(J1-Pad6)") (class "Default")
      (node (ref "J1") (pin "6") (pinfunction "6_6") (pintype "passive"))
    )
    (net (code "42") (name "unconnected-(J1-Pad7)") (class "Default")
      (node (ref "J1") (pin "7") (pinfunction "7_7") (pintype "passive"))
    )
    (net (code "43") (name "unconnected-(J1-Pad8)") (class "Default")
      (node (ref "J1") (pin "8") (pinfunction "8_8") (pintype "passive"))
    )
    (net (code "44") (name "unconnected-(J1-Pad9)") (class "Default")
      (node (ref "J1") (pin "9") (pinfunction "9_9") (pintype "passive"))
    )
    (net (code "45") (name "unconnected-(J1-Pad10)") (class "Default")
      (node (ref "J1") (pin "10") (pinfunction "10_10") (pintype "passive"))
    )
    (net (code "46") (name "~{SD}") (class "Default")
      (node (ref "CF1.2") (pin "39") (pinfunction "39_39") (pintype "passive"))
      (node (ref "CF1.2") (pin "40") (pinfunction "40_40") (pintype "passive"))
      (node (ref "CF2.2") (pin "39") (pinfunction "39_39") (pintype "passive"))
      (node (ref "CF2.2") (pin "40") (pinfunction "40_40") (pintype "passive"))
      (node (ref "CF3.2") (pin "39") (pinfunction "39_39") (pintype "passive"))
      (node (ref "CF3.2") (pin "40") (pinfunction "40_40") (pintype "passive"))
      (node (ref "CF4.2") (pin "39") (pinfunction "39_39") (pintype "passive"))
      (node (ref "CF4.2") (pin "40") (pinfunction "40_40") (pintype "passive"))
      (node (ref "CF5.2") (pin "39") (pinfunction "39_39") (pintype "passive"))
      (node (ref "CF5.2") (pin "40") (pinfunction "40_40") (pintype "passive"))
      (node (ref "CF6.2") (pin "39") (pinfunction "39_39") (pintype "passive"))
      (node (ref "CF6.2") (pin "40") (pinfunction "40_40") (pintype "passive"))
      (node (ref "CF7.2") (pin "39") (pinfunction "39_39") (pintype "passive"))
      (node (ref "CF7.2") (pin "40") (pinfunction "40_40") (pintype "passive"))
      (node (ref "J2") (pin "1") (pinfunction "1_1") (pintype "passive"))
    )
  )
)
